# Power_Supplies.net
KiCad netlist of a schematic drawn in Altium Designer
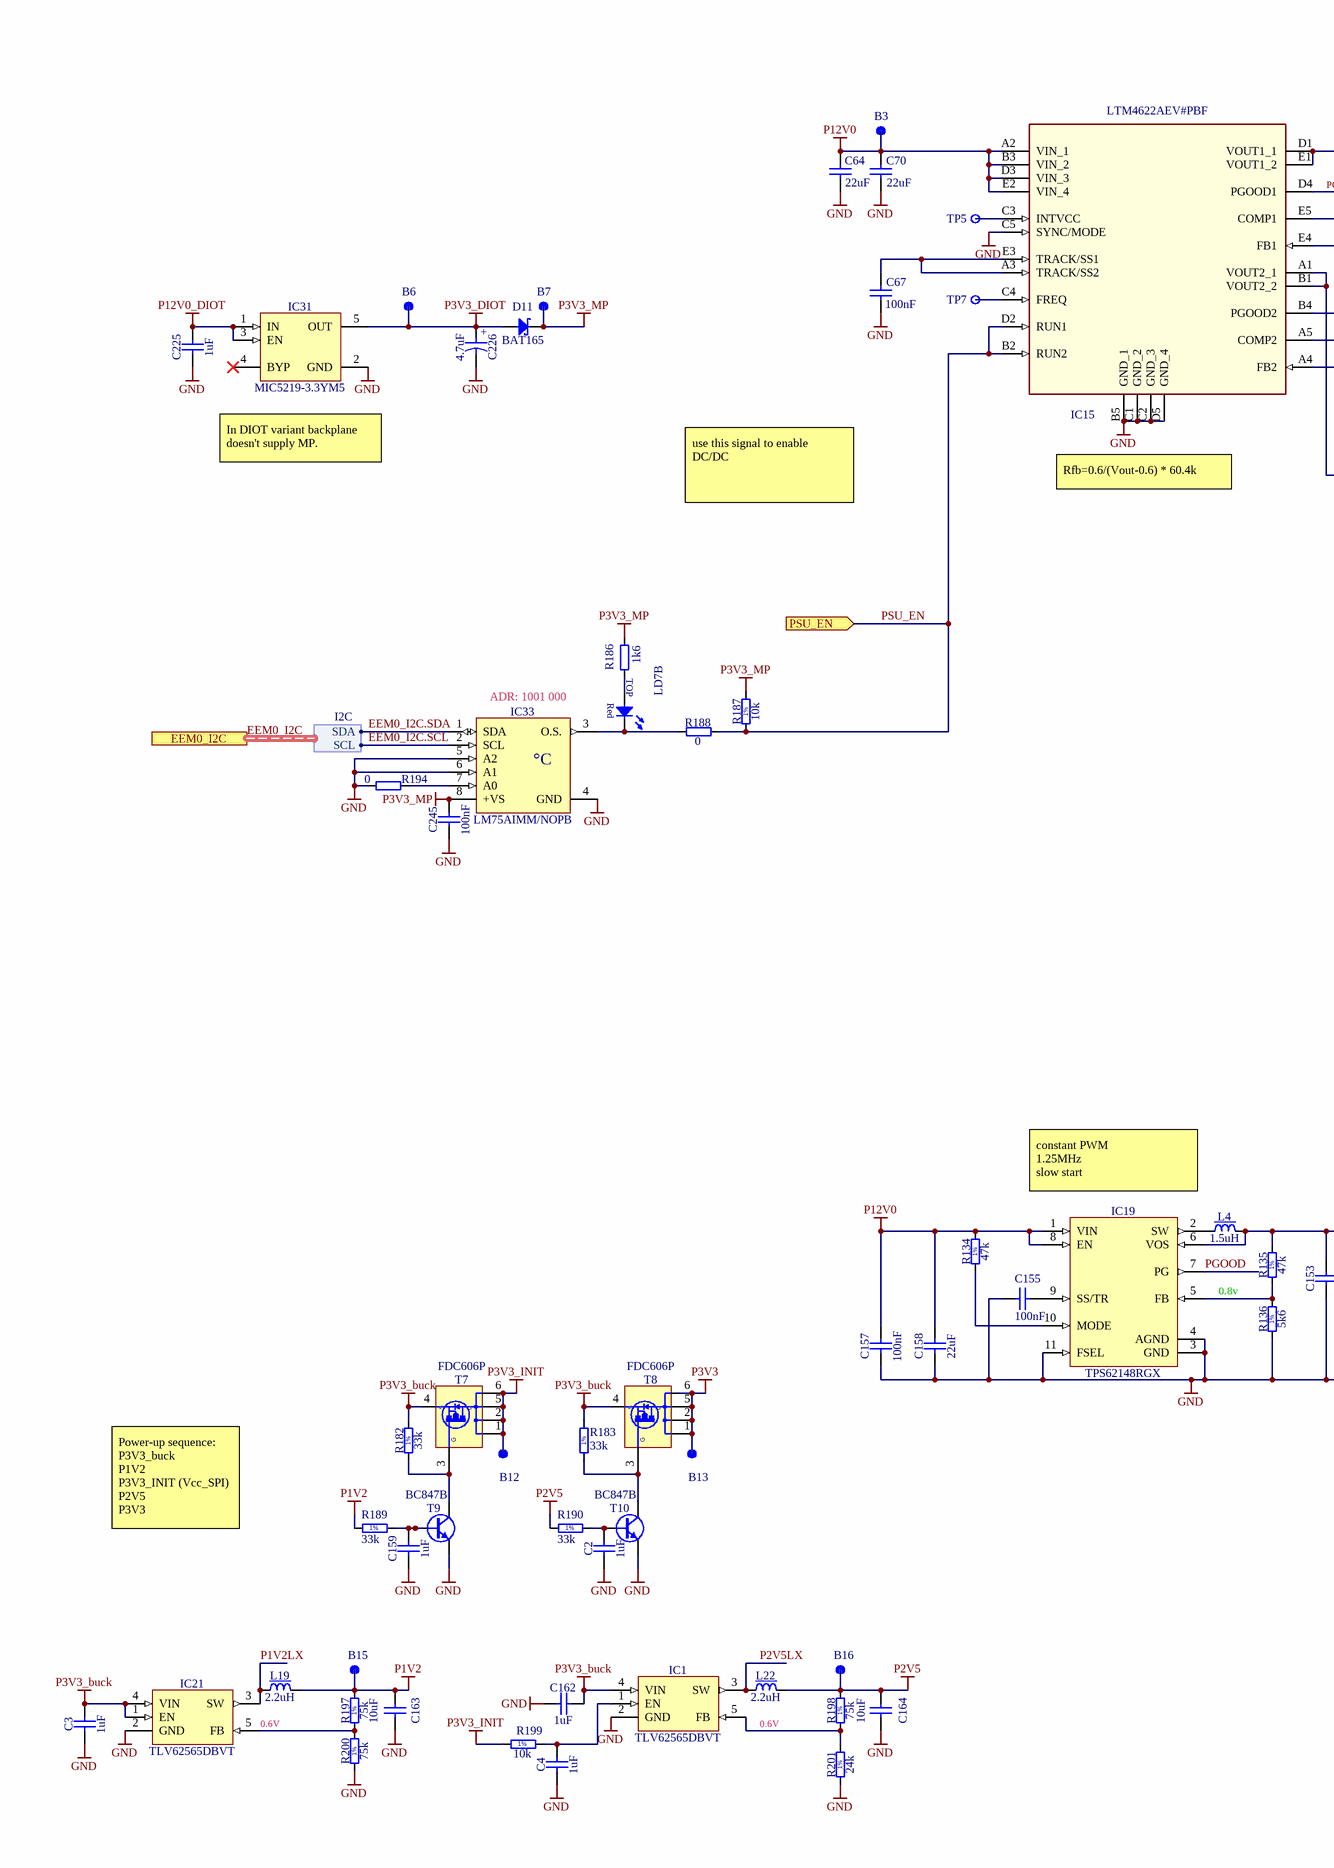
[diagram p0: Power_Supplies.SchDoc, left]
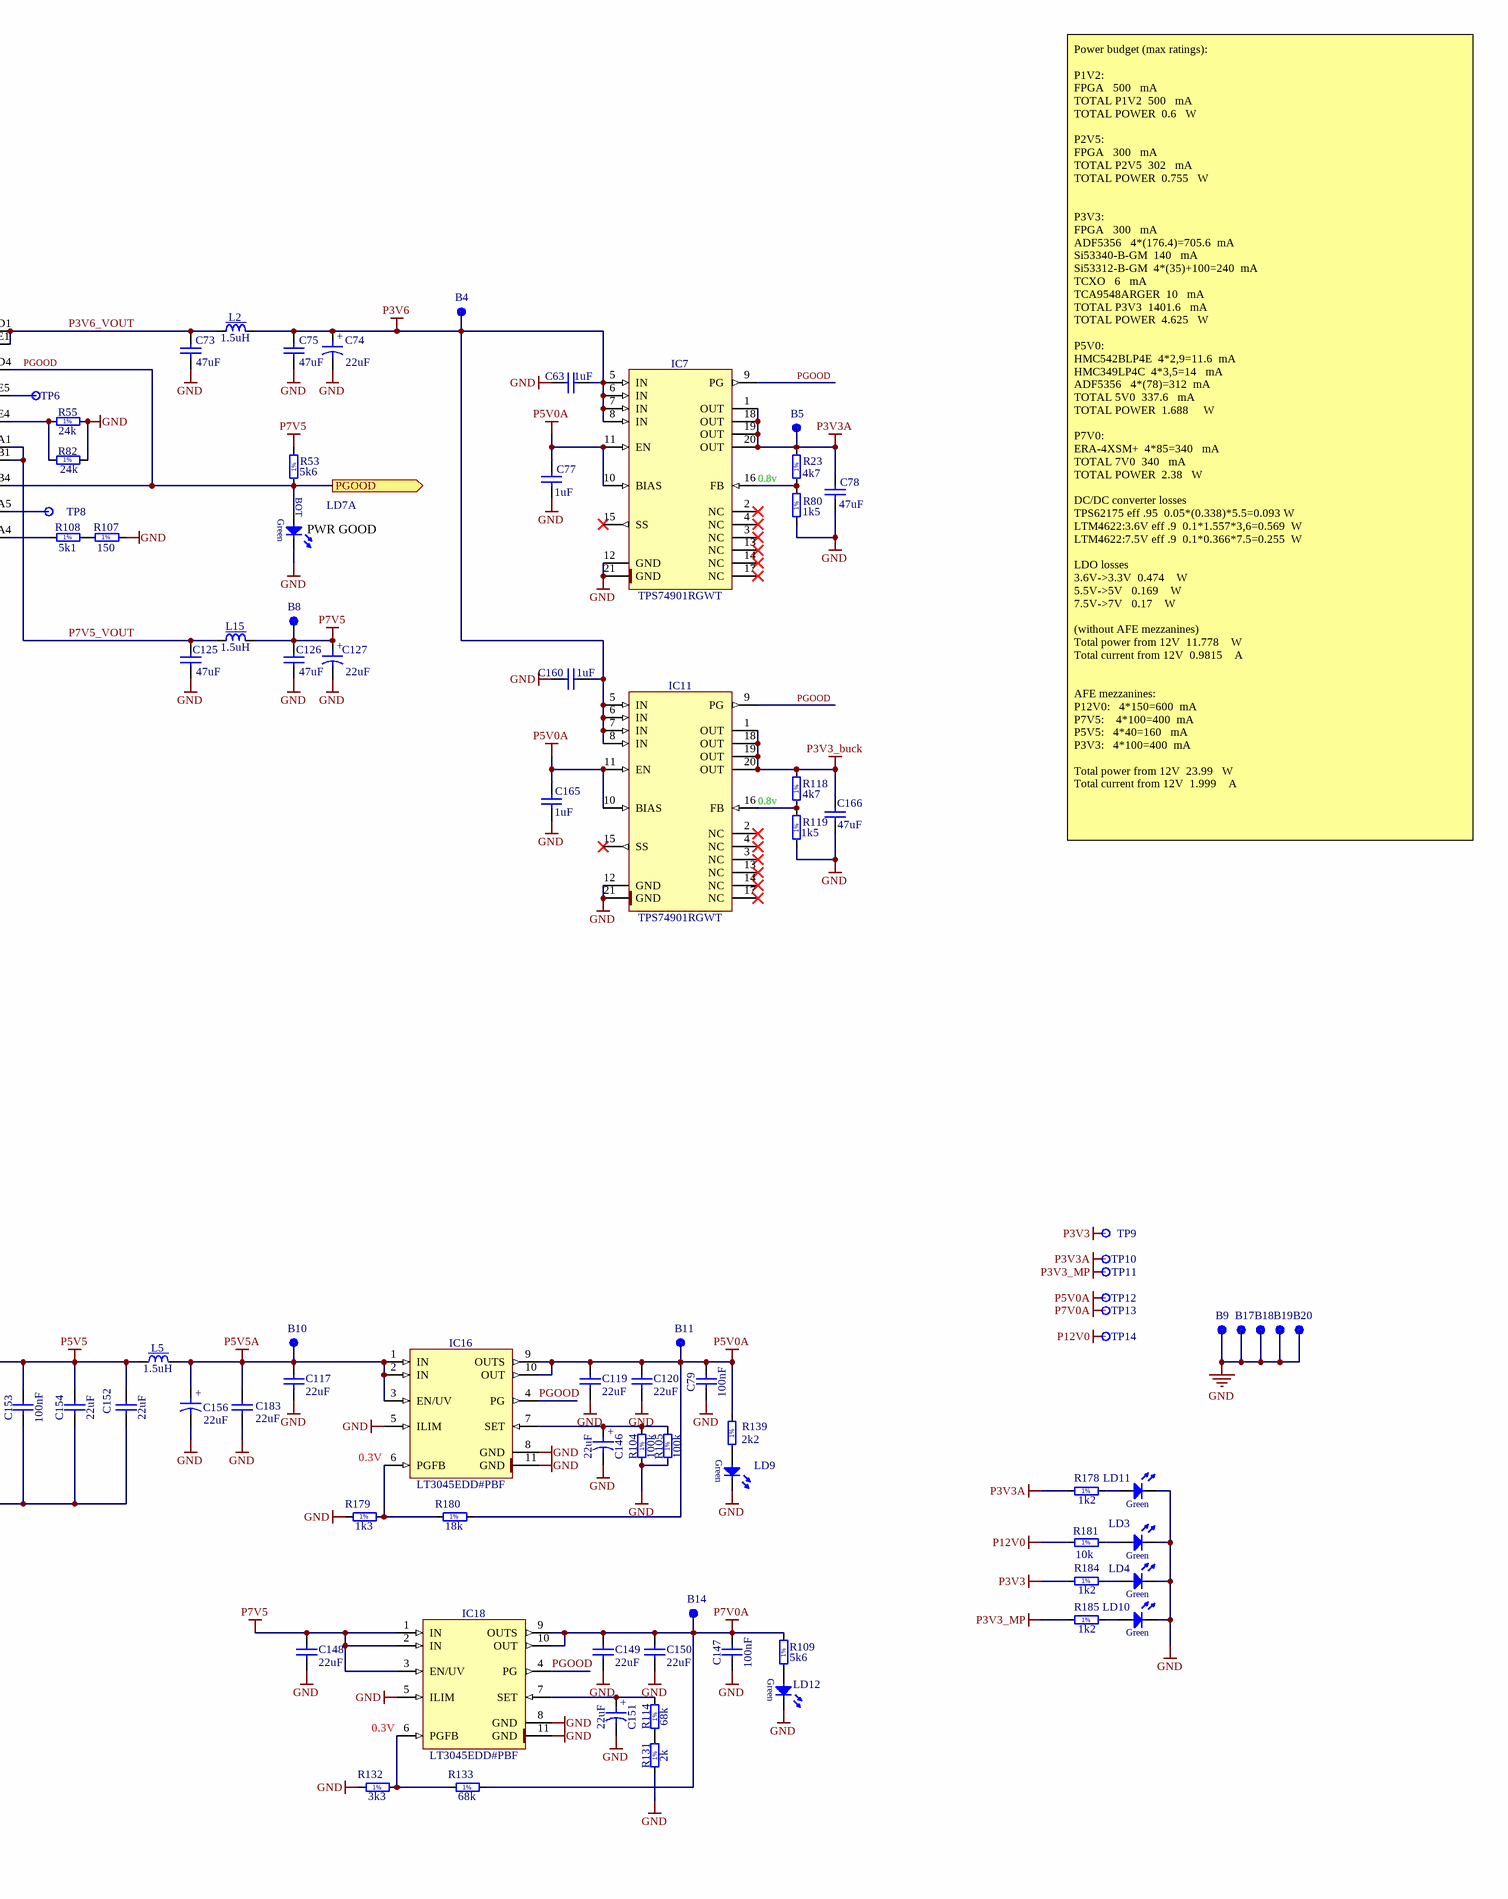
[diagram p1: Power_Supplies.SchDoc, right]

(export (version "E")
  (design (tool "Eeschema 10.0.6"))
  (components
    (comp (ref "B3")
      (value "SMD Pad")
      (footprint "C75")
      (description "Pad")
      (fields (field (name "PART NUMBER") "SMD_PAD_D0.75MM") (field (name "AUTHOR") "CERN DEM BC"))
      (libsource (lib "Eletro-mechanical") (part "Single SMD Pad (Round)"))
    )
    (comp (ref "B4")
      (value "SMD Pad")
      (footprint "C75")
      (description "Pad")
      (fields (field (name "PART NUMBER") "SMD_PAD_D0.75MM") (field (name "AUTHOR") "CERN DEM BC"))
      (libsource (lib "Eletro-mechanical") (part "Single SMD Pad (Round)"))
    )
    (comp (ref "B5")
      (value "SMD Pad")
      (footprint "C75")
      (description "Pad")
      (fields (field (name "PART NUMBER") "SMD_PAD_D0.75MM") (field (name "AUTHOR") "CERN DEM BC"))
      (libsource (lib "Eletro-mechanical") (part "Single SMD Pad (Round)"))
    )
    (comp (ref "B6")
      (value "SMD Pad")
      (footprint "C75")
      (description "Pad")
      (fields (field (name "PART NUMBER") "SMD_PAD_D0.75MM") (field (name "AUTHOR") "CERN DEM BC"))
      (libsource (lib "Eletro-mechanical") (part "Single SMD Pad (Round)"))
    )
    (comp (ref "B7")
      (value "SMD Pad")
      (footprint "C75")
      (description "Pad")
      (fields (field (name "PART NUMBER") "SMD_PAD_D0.75MM") (field (name "AUTHOR") "CERN DEM BC"))
      (libsource (lib "Eletro-mechanical") (part "Single SMD Pad (Round)"))
    )
    (comp (ref "B8")
      (value "SMD Pad")
      (footprint "C75")
      (description "Pad")
      (fields (field (name "PART NUMBER") "SMD_PAD_D0.75MM") (field (name "AUTHOR") "CERN DEM BC"))
      (libsource (lib "Eletro-mechanical") (part "Single SMD Pad (Round)"))
    )
    (comp (ref "B9")
      (value "SMD Pad")
      (footprint "C75")
      (description "Pad")
      (fields (field (name "PART NUMBER") "SMD_PAD_D0.75MM") (field (name "AUTHOR") "CERN DEM BC"))
      (libsource (lib "Eletro-mechanical") (part "Single SMD Pad (Round)"))
    )
    (comp (ref "B10")
      (value "SMD Pad")
      (footprint "C75")
      (description "Pad")
      (fields (field (name "PART NUMBER") "SMD_PAD_D0.75MM") (field (name "AUTHOR") "CERN DEM BC"))
      (libsource (lib "Eletro-mechanical") (part "Single SMD Pad (Round)"))
    )
    (comp (ref "B11")
      (value "SMD Pad")
      (footprint "C75")
      (description "Pad")
      (fields (field (name "PART NUMBER") "SMD_PAD_D0.75MM") (field (name "AUTHOR") "CERN DEM BC"))
      (libsource (lib "Eletro-mechanical") (part "Single SMD Pad (Round)"))
    )
    (comp (ref "B12")
      (value "SMD Pad")
      (footprint "C75")
      (description "Pad")
      (fields (field (name "PART NUMBER") "SMD_PAD_D0.75MM") (field (name "AUTHOR") "CERN DEM BC"))
      (libsource (lib "Eletro-mechanical") (part "Single SMD Pad (Round)"))
    )
    (comp (ref "B13")
      (value "SMD Pad")
      (footprint "C75")
      (description "Pad")
      (fields (field (name "PART NUMBER") "SMD_PAD_D0.75MM") (field (name "AUTHOR") "CERN DEM BC"))
      (libsource (lib "Eletro-mechanical") (part "Single SMD Pad (Round)"))
    )
    (comp (ref "B14")
      (value "SMD Pad")
      (footprint "C75")
      (description "Pad")
      (fields (field (name "PART NUMBER") "SMD_PAD_D0.75MM") (field (name "AUTHOR") "CERN DEM BC"))
      (libsource (lib "Eletro-mechanical") (part "Single SMD Pad (Round)"))
    )
    (comp (ref "B15")
      (value "SMD Pad")
      (footprint "C75")
      (description "Pad")
      (fields (field (name "PART NUMBER") "SMD_PAD_D0.75MM") (field (name "AUTHOR") "CERN DEM BC"))
      (libsource (lib "Eletro-mechanical") (part "Single SMD Pad (Round)"))
    )
    (comp (ref "B16")
      (value "SMD Pad")
      (footprint "C75")
      (description "Pad")
      (fields (field (name "PART NUMBER") "SMD_PAD_D0.75MM") (field (name "AUTHOR") "CERN DEM BC"))
      (libsource (lib "Eletro-mechanical") (part "Single SMD Pad (Round)"))
    )
    (comp (ref "B17")
      (value "SMD Pad")
      (footprint "C75")
      (description "Pad")
      (fields (field (name "PART NUMBER") "SMD_PAD_D0.75MM") (field (name "AUTHOR") "CERN DEM BC"))
      (libsource (lib "Eletro-mechanical") (part "Single SMD Pad (Round)"))
    )
    (comp (ref "B18")
      (value "SMD Pad")
      (footprint "C75")
      (description "Pad")
      (fields (field (name "PART NUMBER") "SMD_PAD_D0.75MM") (field (name "AUTHOR") "CERN DEM BC"))
      (libsource (lib "Eletro-mechanical") (part "Single SMD Pad (Round)"))
    )
    (comp (ref "B19")
      (value "SMD Pad")
      (footprint "C75")
      (description "Pad")
      (fields (field (name "PART NUMBER") "SMD_PAD_D0.75MM") (field (name "AUTHOR") "CERN DEM BC"))
      (libsource (lib "Eletro-mechanical") (part "Single SMD Pad (Round)"))
    )
    (comp (ref "B20")
      (value "SMD Pad")
      (footprint "C75")
      (description "Pad")
      (fields (field (name "PART NUMBER") "SMD_PAD_D0.75MM") (field (name "AUTHOR") "CERN DEM BC"))
      (libsource (lib "Eletro-mechanical") (part "Single SMD Pad (Round)"))
    )
    (comp (ref "C2")
      (value "1uF")
      (footprint "CAPC1608X87N")
      (description "Non-polarised capacitor")
      (fields
        (field (name "PART NUMBER") "CC0603_1UF_25V_10%_X7R")
        (field (name "VOLTAGE") "25V")
        (field (name "AUTHOR") "CERN DEM JLC")
      )
      (libsource (lib "Capacitors") (part "Capacitor - non polarized"))
    )
    (comp (ref "C3")
      (value "1uF")
      (footprint "CAPC1005X55N")
      (description "Non-polarised capacitor")
      (fields
        (field (name "PART NUMBER") "CC0402_1UF_16V_10%_X5R")
        (field (name "VOLTAGE") "16V")
        (field (name "AUTHOR") "CERN DEM JLC")
      )
      (libsource (lib "Capacitors") (part "Capacitor - non polarized"))
    )
    (comp (ref "C4")
      (value "1uF")
      (footprint "CAPC1608X87N")
      (description "Non-polarised capacitor")
      (fields
        (field (name "PART NUMBER") "CC0603_1UF_25V_10%_X7R")
        (field (name "VOLTAGE") "25V")
        (field (name "AUTHOR") "CERN DEM JLC")
      )
      (libsource (lib "Capacitors") (part "Capacitor - non polarized"))
    )
    (comp (ref "C63")
      (value "1uF")
      (footprint "CAPC1005X55N")
      (description "Non-polarised capacitor")
      (fields
        (field (name "PART NUMBER") "CC0402_1UF_16V_10%_X5R")
        (field (name "VOLTAGE") "16V")
        (field (name "AUTHOR") "CERN DEM JLC")
      )
      (libsource (lib "Capacitors") (part "Capacitor - non polarized"))
    )
    (comp (ref "C64")
      (value "22uF")
      (footprint "CAPC2012X135N")
      (description "Non-polarised capacitor")
      (fields
        (field (name "PART NUMBER") "CC0805_22UF_16V_10%_X5R")
        (field (name "VOLTAGE") "16V")
        (field (name "AUTHOR") "CERN DEM JLC")
      )
      (libsource (lib "Capacitors") (part "Capacitor - non polarized"))
    )
    (comp (ref "C67")
      (value "100nF")
      (footprint "CAPC1005X55N")
      (description "Non-polarised capacitor")
      (fields
        (field (name "PART NUMBER") "CC0402_100NF_16V_10%_X5R")
        (field (name "VOLTAGE") "16V")
        (field (name "AUTHOR") "CERN DEM JLC")
      )
      (libsource (lib "Capacitors") (part "Capacitor - non polarized"))
    )
    (comp (ref "C70")
      (value "22uF")
      (footprint "CAPC2012X135N")
      (description "Non-polarised capacitor")
      (fields
        (field (name "PART NUMBER") "CC0805_22UF_16V_10%_X5R")
        (field (name "VOLTAGE") "16V")
        (field (name "AUTHOR") "CERN DEM JLC")
      )
      (libsource (lib "Capacitors") (part "Capacitor - non polarized"))
    )
    (comp (ref "C73")
      (value "47uF")
      (footprint "CAPC3225X270N")
      (description "Non-polarised capacitor")
      (fields
        (field (name "PART NUMBER") "CC1210_47UF_10V_20%_X5R")
        (field (name "VOLTAGE") "10V")
        (field (name "AUTHOR") "CERN DEM JLC")
      )
      (libsource (lib "Capacitors") (part "Capacitor - non polarized"))
    )
    (comp (ref "C74")
      (value "22uF")
      (footprint "CAPMP3528X210N")
      (description "Polarised capacitor")
      (fields
        (field (name "PART NUMBER") "CTE3528-21_22UF_10V_10%_LESR0700")
        (field (name "VOLTAGE") "10V")
        (field (name "AUTHOR") "CERN DEM JLC")
      )
      (libsource (lib "Capacitors") (part "Capacitor - polarized"))
    )
    (comp (ref "C75")
      (value "47uF")
      (footprint "CAPC3225X270N")
      (description "Non-polarised capacitor")
      (fields
        (field (name "PART NUMBER") "CC1210_47UF_10V_20%_X5R")
        (field (name "VOLTAGE") "10V")
        (field (name "AUTHOR") "CERN DEM JLC")
      )
      (libsource (lib "Capacitors") (part "Capacitor - non polarized"))
    )
    (comp (ref "C77")
      (value "1uF")
      (footprint "CAPC1005X55N")
      (description "Non-polarised capacitor")
      (fields
        (field (name "PART NUMBER") "CC0402_1UF_16V_10%_X5R")
        (field (name "VOLTAGE") "16V")
        (field (name "AUTHOR") "CERN DEM JLC")
      )
      (libsource (lib "Capacitors") (part "Capacitor - non polarized"))
    )
    (comp (ref "C78")
      (value "47uF")
      (footprint "CAPC3225X270N")
      (description "Non-polarised capacitor")
      (fields
        (field (name "PART NUMBER") "CC1210_47UF_10V_20%_X5R")
        (field (name "VOLTAGE") "10V")
        (field (name "AUTHOR") "CERN DEM JLC")
      )
      (libsource (lib "Capacitors") (part "Capacitor - non polarized"))
    )
    (comp (ref "C79")
      (value "100nF")
      (footprint "CAPC1005X55N")
      (description "Non-polarised capacitor")
      (fields
        (field (name "PART NUMBER") "CC0402_100NF_16V_10%_X5R")
        (field (name "VOLTAGE") "16V")
        (field (name "AUTHOR") "CERN DEM JLC")
      )
      (libsource (lib "Capacitors") (part "Capacitor - non polarized"))
    )
    (comp (ref "C117")
      (value "22uF")
      (footprint "CAPC2012X135N")
      (description "Non-polarised capacitor")
      (fields
        (field (name "PART NUMBER") "CC0805_22UF_16V_10%_X5R")
        (field (name "VOLTAGE") "16V")
        (field (name "AUTHOR") "CERN DEM JLC")
      )
      (libsource (lib "Capacitors") (part "Capacitor - non polarized"))
    )
    (comp (ref "C119")
      (value "22uF")
      (footprint "CAPC2012X135N")
      (description "Non-polarised capacitor")
      (fields
        (field (name "PART NUMBER") "CC0805_22UF_16V_10%_X5R")
        (field (name "VOLTAGE") "16V")
        (field (name "AUTHOR") "CERN DEM JLC")
      )
      (libsource (lib "Capacitors") (part "Capacitor - non polarized"))
    )
    (comp (ref "C120")
      (value "22uF")
      (footprint "CAPC2012X135N")
      (description "Non-polarised capacitor")
      (fields
        (field (name "PART NUMBER") "CC0805_22UF_16V_10%_X5R")
        (field (name "VOLTAGE") "16V")
        (field (name "AUTHOR") "CERN DEM JLC")
      )
      (libsource (lib "Capacitors") (part "Capacitor - non polarized"))
    )
    (comp (ref "C125")
      (value "47uF")
      (footprint "CAPC3225X270N")
      (description "Non-polarised capacitor")
      (fields
        (field (name "PART NUMBER") "CC1210_47UF_10V_20%_X5R")
        (field (name "VOLTAGE") "10V")
        (field (name "AUTHOR") "CERN DEM JLC")
      )
      (libsource (lib "Capacitors") (part "Capacitor - non polarized"))
    )
    (comp (ref "C126")
      (value "47uF")
      (footprint "CAPC3225X270N")
      (description "Non-polarised capacitor")
      (fields
        (field (name "PART NUMBER") "CC1210_47UF_10V_20%_X5R")
        (field (name "VOLTAGE") "10V")
        (field (name "AUTHOR") "CERN DEM JLC")
      )
      (libsource (lib "Capacitors") (part "Capacitor - non polarized"))
    )
    (comp (ref "C127")
      (value "22uF")
      (footprint "CAPMP3528X210N")
      (description "Polarised capacitor")
      (fields
        (field (name "PART NUMBER") "CTE3528-21_22UF_10V_10%_LESR0700")
        (field (name "VOLTAGE") "10V")
        (field (name "AUTHOR") "CERN DEM JLC")
      )
      (libsource (lib "Capacitors") (part "Capacitor - polarized"))
    )
    (comp (ref "C146")
      (value "22uF")
      (footprint "CAPMP3528X210N")
      (description "Polarised capacitor")
      (fields
        (field (name "PART NUMBER") "CTE3528-21_22UF_10V_10%_LESR0700")
        (field (name "VOLTAGE") "10V")
        (field (name "AUTHOR") "CERN DEM JLC")
      )
      (libsource (lib "Capacitors") (part "Capacitor - polarized"))
    )
    (comp (ref "C147")
      (value "100nF")
      (footprint "CAPC1005X55N")
      (description "Non-polarised capacitor")
      (fields
        (field (name "PART NUMBER") "CC0402_100NF_16V_10%_X5R")
        (field (name "VOLTAGE") "16V")
        (field (name "AUTHOR") "CERN DEM JLC")
      )
      (libsource (lib "Capacitors") (part "Capacitor - non polarized"))
    )
    (comp (ref "C148")
      (value "22uF")
      (footprint "CAPC2012X135N")
      (description "Non-polarised capacitor")
      (fields
        (field (name "PART NUMBER") "CC0805_22UF_16V_10%_X5R")
        (field (name "VOLTAGE") "16V")
        (field (name "AUTHOR") "CERN DEM JLC")
      )
      (libsource (lib "Capacitors") (part "Capacitor - non polarized"))
    )
    (comp (ref "C149")
      (value "22uF")
      (footprint "CAPC2012X135N")
      (description "Non-polarised capacitor")
      (fields
        (field (name "PART NUMBER") "CC0805_22UF_16V_10%_X5R")
        (field (name "VOLTAGE") "16V")
        (field (name "AUTHOR") "CERN DEM JLC")
      )
      (libsource (lib "Capacitors") (part "Capacitor - non polarized"))
    )
    (comp (ref "C150")
      (value "22uF")
      (footprint "CAPC2012X135N")
      (description "Non-polarised capacitor")
      (fields
        (field (name "PART NUMBER") "CC0805_22UF_16V_10%_X5R")
        (field (name "VOLTAGE") "16V")
        (field (name "AUTHOR") "CERN DEM JLC")
      )
      (libsource (lib "Capacitors") (part "Capacitor - non polarized"))
    )
    (comp (ref "C151")
      (value "22uF")
      (footprint "CAPMP3528X210N")
      (description "Polarised capacitor")
      (fields
        (field (name "PART NUMBER") "CTE3528-21_22UF_10V_10%_LESR0700")
        (field (name "VOLTAGE") "10V")
        (field (name "AUTHOR") "CERN DEM JLC")
      )
      (libsource (lib "Capacitors") (part "Capacitor - polarized"))
    )
    (comp (ref "C152")
      (value "22uF")
      (footprint "CAPC2012X135N")
      (description "Non-polarised capacitor")
      (fields
        (field (name "PART NUMBER") "CC0805_22UF_16V_10%_X5R")
        (field (name "VOLTAGE") "16V")
        (field (name "AUTHOR") "CERN DEM JLC")
      )
      (libsource (lib "Capacitors") (part "Capacitor - non polarized"))
    )
    (comp (ref "C153")
      (value "100nF")
      (footprint "CAPC1005X55N")
      (description "Non-polarised capacitor")
      (fields
        (field (name "PART NUMBER") "CC0402_100NF_16V_10%_X5R")
        (field (name "VOLTAGE") "16V")
        (field (name "AUTHOR") "CERN DEM JLC")
      )
      (libsource (lib "Capacitors") (part "Capacitor - non polarized"))
    )
    (comp (ref "C154")
      (value "22uF")
      (footprint "CAPC2012X135N")
      (description "Non-polarised capacitor")
      (fields
        (field (name "PART NUMBER") "CC0805_22UF_16V_10%_X5R")
        (field (name "VOLTAGE") "16V")
        (field (name "AUTHOR") "CERN DEM JLC")
      )
      (libsource (lib "Capacitors") (part "Capacitor - non polarized"))
    )
    (comp (ref "C155")
      (value "100nF")
      (footprint "CAPC1005X55N")
      (description "Non-polarised capacitor")
      (fields
        (field (name "PART NUMBER") "CC0402_100NF_16V_10%_X5R")
        (field (name "VOLTAGE") "16V")
        (field (name "AUTHOR") "CERN DEM JLC")
      )
      (libsource (lib "Capacitors") (part "Capacitor - non polarized"))
    )
    (comp (ref "C156")
      (value "22uF")
      (footprint "CAPMP3528X210N")
      (description "Polarised capacitor")
      (fields
        (field (name "PART NUMBER") "CTE3528-21_22UF_10V_10%_LESR0700")
        (field (name "VOLTAGE") "10V")
        (field (name "AUTHOR") "CERN DEM JLC")
      )
      (libsource (lib "Capacitors") (part "Capacitor - polarized"))
    )
    (comp (ref "C157")
      (value "100nF")
      (footprint "CAPC1005X55N")
      (description "Non-polarised capacitor")
      (fields
        (field (name "PART NUMBER") "CC0402_100NF_16V_10%_X5R")
        (field (name "VOLTAGE") "16V")
        (field (name "AUTHOR") "CERN DEM JLC")
      )
      (libsource (lib "Capacitors") (part "Capacitor - non polarized"))
    )
    (comp (ref "C158")
      (value "22uF")
      (footprint "CAPC2012X135N")
      (description "Non-polarised capacitor")
      (fields
        (field (name "PART NUMBER") "CC0805_22UF_16V_10%_X5R")
        (field (name "VOLTAGE") "16V")
        (field (name "AUTHOR") "CERN DEM JLC")
      )
      (libsource (lib "Capacitors") (part "Capacitor - non polarized"))
    )
    (comp (ref "C159")
      (value "1uF")
      (footprint "CAPC1608X87N")
      (description "Non-polarised capacitor")
      (fields
        (field (name "PART NUMBER") "CC0603_1UF_25V_10%_X7R")
        (field (name "VOLTAGE") "25V")
        (field (name "AUTHOR") "CERN DEM JLC")
      )
      (libsource (lib "Capacitors") (part "Capacitor - non polarized"))
    )
    (comp (ref "C160")
      (value "1uF")
      (footprint "CAPC1005X55N")
      (description "Non-polarised capacitor")
      (fields
        (field (name "PART NUMBER") "CC0402_1UF_16V_10%_X5R")
        (field (name "VOLTAGE") "16V")
        (field (name "AUTHOR") "CERN DEM JLC")
      )
      (libsource (lib "Capacitors") (part "Capacitor - non polarized"))
    )
    (comp (ref "C162")
      (value "1uF")
      (footprint "CAPC1005X55N")
      (description "Non-polarised capacitor")
      (fields
        (field (name "PART NUMBER") "CC0402_1UF_16V_10%_X5R")
        (field (name "VOLTAGE") "16V")
        (field (name "AUTHOR") "CERN DEM JLC")
      )
      (libsource (lib "Capacitors") (part "Capacitor - non polarized"))
    )
    (comp (ref "C163")
      (value "10uF")
      (footprint "CAPC2012X135N")
      (description "Non-polarised capacitor")
      (fields
        (field (name "PART NUMBER") "CC0805_10UF_16V_10%_X5R")
        (field (name "VOLTAGE") "16V")
        (field (name "AUTHOR") "CERN DEM JLC")
      )
      (libsource (lib "Capacitors") (part "Capacitor - non polarized"))
    )
    (comp (ref "C164")
      (value "10uF")
      (footprint "CAPC2012X135N")
      (description "Non-polarised capacitor")
      (fields
        (field (name "PART NUMBER") "CC0805_10UF_16V_10%_X5R")
        (field (name "VOLTAGE") "16V")
        (field (name "AUTHOR") "CERN DEM JLC")
      )
      (libsource (lib "Capacitors") (part "Capacitor - non polarized"))
    )
    (comp (ref "C165")
      (value "1uF")
      (footprint "CAPC1005X55N")
      (description "Non-polarised capacitor")
      (fields
        (field (name "PART NUMBER") "CC0402_1UF_16V_10%_X5R")
        (field (name "VOLTAGE") "16V")
        (field (name "AUTHOR") "CERN DEM JLC")
      )
      (libsource (lib "Capacitors") (part "Capacitor - non polarized"))
    )
    (comp (ref "C166")
      (value "47uF")
      (footprint "CAPC3225X270N")
      (description "Non-polarised capacitor")
      (fields
        (field (name "PART NUMBER") "CC1210_47UF_10V_20%_X5R")
        (field (name "VOLTAGE") "10V")
        (field (name "AUTHOR") "CERN DEM JLC")
      )
      (libsource (lib "Capacitors") (part "Capacitor - non polarized"))
    )
    (comp (ref "C183")
      (value "22uF")
      (footprint "CAPC2012X135N")
      (description "Non-polarised capacitor")
      (fields
        (field (name "PART NUMBER") "CC0805_22UF_16V_10%_X5R")
        (field (name "VOLTAGE") "16V")
        (field (name "AUTHOR") "CERN DEM JLC")
      )
      (libsource (lib "Capacitors") (part "Capacitor - non polarized"))
    )
    (comp (ref "C225")
      (value "1uF")
      (footprint "CAPC1608X87N")
      (description "Non-polarised capacitor")
      (fields
        (field (name "PART NUMBER") "CC0603_1UF_25V_10%_X7R")
        (field (name "VOLTAGE") "25V")
        (field (name "AUTHOR") "CERN DEM JLC")
      )
      (libsource (lib "Capacitors") (part "Capacitor - non polarized"))
    )
    (comp (ref "C226")
      (value "4.7uF")
      (footprint "CAPMP3216X180N")
      (description "Polarised capacitor")
      (fields
        (field (name "PART NUMBER") "CTE3216-18_4.7UF_10V_10%_AVX_TPSA475K010T1400")
        (field (name "VOLTAGE") "10V")
        (field (name "AUTHOR") "CERN DEM JLC")
      )
      (libsource (lib "Capacitors") (part "Capacitor - polarized"))
    )
    (comp (ref "C245")
      (value "100nF")
      (footprint "CAPC1005X55N")
      (description "Non-polarised capacitor")
      (fields
        (field (name "PART NUMBER") "CC0402_100NF_16V_10%_X5R")
        (field (name "VOLTAGE") "16V")
        (field (name "AUTHOR") "CERN DEM JLC")
      )
      (libsource (lib "Capacitors") (part "Capacitor - non polarized"))
    )
    (comp (ref "D11")
      (value "BAT165")
      (footprint "SOD2512X110N")
      (description "Schottky Diode")
      (fields
        (field (name "MANUFACTURER") "INFINEON")
        (field (name "VOLTAGE") "40V")
        (field (name "AUTHOR") "CERN DEM JLC")
      )
      (libsource (lib "ICs And Semiconductors") (part "Diode Schottky"))
    )
    (comp (ref "IC1")
      (value "TLV62565DBVT")
      (footprint "SOT95P280X145-5N")
      (description "1.5A High Efficiency Step-Down Converter, Adjustable Output Voltage")
      (fields
        (field (name "MANUFACTURER") "TEXAS INSTRUMENTS")
        (field (name "MANUFACTURER PART NUMBER") "TLV62565DBV")
        (field (name "AUTHOR") "CERN DEM JMW")
      )
      (libsource (lib "ICs And Semiconductors") (part "TLV62565"))
    )
    (comp (ref "IC7")
      (value "TPS74901RGWT")
      (footprint "QFN65P500X500X100-21N-S325")
      (description "3A, 0.8 to 3.6V Adjustable Low-Dropout Linear Regulator with Programmable Soft-Start")
      (fields (field (name "MANUFACTURER") "TEXAS INSTRUMENTS") (field (name "AUTHOR") "CERN DEM JLC"))
      (libsource (lib "ICs And Semiconductors") (part "TPS74901RGWT"))
    )
    (comp (ref "IC11")
      (value "TPS74901RGWT")
      (footprint "QFN65P500X500X100-21N-S325")
      (description "3A, 0.8 to 3.6V Adjustable Low-Dropout Linear Regulator with Programmable Soft-Start")
      (fields (field (name "MANUFACTURER") "TEXAS INSTRUMENTS") (field (name "AUTHOR") "CERN DEM JLC"))
      (libsource (lib "ICs And Semiconductors") (part "TPS74901RGWT"))
    )
    (comp (ref "IC15")
      (value "LTM4622AEV#PBF")
      (footprint "LGA25C127P5X5_625X625X190")
      (description "Dual Ultrathin 2A or Single 4A, 3.6V to 20V, 1.5V to 12V   Step-Down DC/DC μModule Regulator")
      (fields (field (name "MANUFACTURER") "LINEAR TECHNOLOGY") (field (name "AUTHOR") "GK"))
      (libsource (lib "LIBRARY_SCH") (part "PM_LTM4622"))
    )
    (comp (ref "IC16")
      (value "LT3045EDD#PBF")
      (footprint "SON50P300X300X80-11N-R175X248")
      (description "20V, 500mA, Ultralow Noise, Ultrahigh PSRR Linear Regulator")
      (fields (field (name "MANUFACTURER") "LINEAR TECHNOLOGY") (field (name "AUTHOR") "CERN DEM JLC"))
      (libsource (lib "ICs And Semiconductors") (part "LT3045EDD"))
    )
    (comp (ref "IC18")
      (value "LT3045EDD#PBF")
      (footprint "SON50P300X300X80-11N-R175X248")
      (description "20V, 500mA, Ultralow Noise, Ultrahigh PSRR Linear Regulator")
      (fields (field (name "MANUFACTURER") "LINEAR TECHNOLOGY") (field (name "AUTHOR") "CERN DEM JLC"))
      (libsource (lib "ICs And Semiconductors") (part "LT3045EDD"))
    )
    (comp (ref "IC19")
      (value "TPS62148RGX")
      (footprint "TEXAS_RGX0011A")
      (description "3V-17V 2A Step-Down Converter, High Accuracy, With DCS-Control")
      (fields (field (name "MANUFACTURER") "TEXAS INSTRUMENTS") (field (name "AUTHOR") "CERN DEM MR"))
      (libsource (lib "ICs And Semiconductors") (part "TPS62148"))
    )
    (comp (ref "IC21")
      (value "TLV62565DBVT")
      (footprint "SOT95P280X145-5N")
      (description "1.5A High Efficiency Step-Down Converter, Adjustable Output Voltage")
      (fields
        (field (name "MANUFACTURER") "TEXAS INSTRUMENTS")
        (field (name "MANUFACTURER PART NUMBER") "TLV62565DBV")
        (field (name "AUTHOR") "CERN DEM JMW")
      )
      (libsource (lib "ICs And Semiconductors") (part "TLV62565"))
    )
    (comp (ref "IC31")
      (value "MIC5219-3.3YM5")
      (footprint "SOT95P280X145-5N")
      (description "500mA Peak Output LDO Regulator")
      (fields (field (name "MANUFACTURER") "MICROCHIP TECHNOLOGY") (field (name "AUTHOR") "CERN DEM WB"))
      (libsource (lib "ICs And Semiconductors") (part "MIC5219-X.XYM5"))
    )
    (comp (ref "IC33")
      (value "LM75AIMM/NOPB")
      (footprint "SOP65P490X109-8N")
      (description "Digital Temperature Sensor and Thermal Watchdog with Two-Wire Interface")
      (fields (field (name "MANUFACTURER") "TEXAS INSTRUMENTS") (field (name "AUTHOR") "CERN DEM JLC"))
      (libsource (lib "ICs And Semiconductors") (part "LM75"))
    )
    (comp (ref "L2")
      (value "1.5uH")
      (footprint "IND_TDK_SPM6530")
      (description "Inductor With Core")
      (fields
        (field (name "PART NUMBER") "IND_1.5UH_20%_TDK_SPM6530")
        (field (name "POWER") "11A")
        (field (name "AUTHOR") "CERN DEM MR")
      )
      (libsource (lib "Inductors & Transformers") (part "Inductor With Magnetic core"))
    )
    (comp (ref "L4")
      (value "1.5uH")
      (footprint "IND_TDK_SPM6530")
      (description "Inductor With Core")
      (fields
        (field (name "PART NUMBER") "IND_1.5UH_20%_TDK_SPM6530")
        (field (name "POWER") "11A")
        (field (name "AUTHOR") "CERN DEM MR")
      )
      (libsource (lib "Inductors & Transformers") (part "Inductor With Magnetic core"))
    )
    (comp (ref "L5")
      (value "1.5uH")
      (footprint "IND_TDK_SPM6530")
      (description "Inductor With Core")
      (fields
        (field (name "PART NUMBER") "IND_1.5UH_20%_TDK_SPM6530")
        (field (name "POWER") "11A")
        (field (name "AUTHOR") "CERN DEM MR")
      )
      (libsource (lib "Inductors & Transformers") (part "Inductor With Magnetic core"))
    )
    (comp (ref "L15")
      (value "1.5uH")
      (footprint "IND_TDK_SPM6530")
      (description "Inductor With Core")
      (fields
        (field (name "PART NUMBER") "IND_1.5UH_20%_TDK_SPM6530")
        (field (name "POWER") "11A")
        (field (name "AUTHOR") "CERN DEM MR")
      )
      (libsource (lib "Inductors & Transformers") (part "Inductor With Magnetic core"))
    )
    (comp (ref "L19")
      (value "2.2uH")
      (footprint "IND_MURATA_LQH44PN_P0")
      (description "Inductor With Core")
      (fields
        (field (name "PART NUMBER") "IND_2.2UH_20%_MURATA_LQH44PN2R2MP0L")
        (field (name "POWER") "1.8A")
        (field (name "AUTHOR") "CERN DEM JLC")
      )
      (libsource (lib "Inductors & Transformers") (part "Inductor With Magnetic core"))
    )
    (comp (ref "L22")
      (value "2.2uH")
      (footprint "IND_MURATA_LQH44PN_P0")
      (description "Inductor With Core")
      (fields
        (field (name "PART NUMBER") "IND_2.2UH_20%_MURATA_LQH44PN2R2MP0L")
        (field (name "POWER") "1.8A")
        (field (name "AUTHOR") "CERN DEM JLC")
      )
      (libsource (lib "Inductors & Transformers") (part "Inductor With Magnetic core"))
    )
    (comp (ref "LD3")
      (value "Green")
      (footprint "LED_KINGBRIGHT_KPH-1608CGCKr")
      (description "Green 0603")
      (fields
        (field (name "PART NUMBER") "LED_KINGBRIGHT_KPH-1608CGCK")
        (field (name "MANUFACTURER") "KINGBRIGHT")
        (field (name "AUTHOR") "CERN DEM JLC")
      )
      (libsource (lib "LIBRARY_SCH") (part "LED_0603_Green"))
    )
    (comp (ref "LD4")
      (value "Green")
      (footprint "LED_KINGBRIGHT_KPH-1608CGCKr")
      (description "Green 0603")
      (fields
        (field (name "PART NUMBER") "LED_KINGBRIGHT_KPH-1608CGCK")
        (field (name "MANUFACTURER") "KINGBRIGHT")
        (field (name "AUTHOR") "CERN DEM JLC")
      )
      (libsource (lib "LIBRARY_SCH") (part "LED_0603_Green"))
    )
    (comp (ref "LD7")
      (value "Red/Green")
      (footprint "LED_DIALIGHT_571-0112F")
      (description "2x LED  Botom Green, Top Red")
      (fields
        (field (name "PART NUMBER") "LED_DIALIGHT_571-0112F")
        (field (name "MANUFACTURER") "DIALIGHT")
        (field (name "AUTHOR") "CERN DEM JLC")
      )
      (libsource (lib "ICs And Semiconductors") (part "LED x2 G-1C2A-BOT_R-3C4A-TOP"))
    )
    (comp (ref "LD9")
      (value "Green")
      (footprint "LED_KINGBRIGHT_KPH-1608CGCKr")
      (description "Green 0603")
      (fields
        (field (name "PART NUMBER") "LED_KINGBRIGHT_KPH-1608CGCK")
        (field (name "MANUFACTURER") "KINGBRIGHT")
        (field (name "AUTHOR") "CERN DEM JLC")
      )
      (libsource (lib "LIBRARY_SCH") (part "LED_0603_Green"))
    )
    (comp (ref "LD10")
      (value "Green")
      (footprint "LED_KINGBRIGHT_KPH-1608CGCKr")
      (description "Green 0603")
      (fields
        (field (name "PART NUMBER") "LED_KINGBRIGHT_KPH-1608CGCK")
        (field (name "MANUFACTURER") "KINGBRIGHT")
        (field (name "AUTHOR") "CERN DEM JLC")
      )
      (libsource (lib "LIBRARY_SCH") (part "LED_0603_Green"))
    )
    (comp (ref "LD11")
      (value "Green")
      (footprint "LED_KINGBRIGHT_KPH-1608CGCKr")
      (description "Green 0603")
      (fields
        (field (name "PART NUMBER") "LED_KINGBRIGHT_KPH-1608CGCK")
        (field (name "MANUFACTURER") "KINGBRIGHT")
        (field (name "AUTHOR") "CERN DEM JLC")
      )
      (libsource (lib "LIBRARY_SCH") (part "LED_0603_Green"))
    )
    (comp (ref "LD12")
      (value "Green")
      (footprint "LED_KINGBRIGHT_KPH-1608CGCKr")
      (description "Green 0603")
      (fields
        (field (name "PART NUMBER") "LED_KINGBRIGHT_KPH-1608CGCK")
        (field (name "MANUFACTURER") "KINGBRIGHT")
        (field (name "AUTHOR") "CERN DEM JLC")
      )
      (libsource (lib "LIBRARY_SCH") (part "LED_0603_Green"))
    )
    (comp (ref "R23")
      (value "4k7")
      (footprint "RESC1608X55N")
      (description "Resistor - 1%")
      (fields
        (field (name "PART NUMBER") "R0603_4K7_1%_0.1W_100PPM")
        (field (name "POWER") "0.1W")
        (field (name "AUTHOR") "CERN DEM JLC")
      )
      (libsource (lib "Resistors") (part "Resistor - 1%"))
    )
    (comp (ref "R53")
      (value "5k6")
      (footprint "RESC1608X55N")
      (description "Resistor - 1%")
      (fields
        (field (name "PART NUMBER") "R0603_5K6_1%_0.1W_100PPM")
        (field (name "POWER") "0.1W")
        (field (name "AUTHOR") "CERN DEM JLC")
      )
      (libsource (lib "Resistors") (part "Resistor - 1%"))
    )
    (comp (ref "R55")
      (value "24k")
      (footprint "RESC1608X55N")
      (description "Resistor - 1%")
      (fields
        (field (name "PART NUMBER") "R0603_24K_1%_0.1W_100PPM")
        (field (name "POWER") "0.1W")
        (field (name "AUTHOR") "CERN DEM JLC")
      )
      (libsource (lib "Resistors") (part "Resistor - 1%"))
    )
    (comp (ref "R80")
      (value "1k5")
      (footprint "RESC1608X55N")
      (description "Resistor - 1%")
      (fields
        (field (name "PART NUMBER") "R0603_1K5_1%_0.1W_100PPM")
        (field (name "POWER") "0.1W")
        (field (name "AUTHOR") "CERN DEM JLC")
      )
      (libsource (lib "Resistors") (part "Resistor - 1%"))
    )
    (comp (ref "R82")
      (value "24k")
      (footprint "RESC1608X55N")
      (description "Resistor - 1%")
      (fields
        (field (name "PART NUMBER") "R0603_24K_1%_0.1W_100PPM")
        (field (name "POWER") "0.1W")
        (field (name "AUTHOR") "CERN DEM JLC")
      )
      (libsource (lib "Resistors") (part "Resistor - 1%"))
    )
    (comp (ref "R104")
      (value "100k")
      (footprint "RESC1005X40N")
      (description "Resistor - 1%")
      (fields
        (field (name "PART NUMBER") "R0402_100K_1%_0.0625W_100PPM")
        (field (name "POWER") "0.0625W")
        (field (name "AUTHOR") "CERN DEM JLC")
      )
      (libsource (lib "") (part "Resistor - 1%_1"))
    )
    (comp (ref "R105")
      (value "100k")
      (footprint "RESC1005X40N")
      (description "Resistor - 1%")
      (fields
        (field (name "PART NUMBER") "R0402_100K_1%_0.0625W_100PPM")
        (field (name "POWER") "0.0625W")
        (field (name "AUTHOR") "CERN DEM JLC")
      )
      (libsource (lib "") (part "Resistor - 1%_1"))
    )
    (comp (ref "R107")
      (value "150")
      (footprint "RESC1005X40N")
      (description "Resistor - 1%")
      (fields
        (field (name "PART NUMBER") "R0402_150R_1%_0.0625W_100PPM")
        (field (name "POWER") "0.0625W")
        (field (name "AUTHOR") "CERN DEM JLC")
      )
      (libsource (lib "") (part "Resistor - 1%_1"))
    )
    (comp (ref "R108")
      (value "5k1")
      (footprint "RESC1608X55N")
      (description "Resistor - 1%")
      (fields
        (field (name "PART NUMBER") "R0603_5K1_1%_0.1W_100PPM")
        (field (name "POWER") "0.1W")
        (field (name "AUTHOR") "CERN DEM JLC")
      )
      (libsource (lib "Resistors") (part "Resistor - 1%"))
    )
    (comp (ref "R109")
      (value "5k6")
      (footprint "RESC1608X55N")
      (description "Resistor - 1%")
      (fields
        (field (name "PART NUMBER") "R0603_5K6_1%_0.1W_100PPM")
        (field (name "POWER") "0.1W")
        (field (name "AUTHOR") "CERN DEM JLC")
      )
      (libsource (lib "Resistors") (part "Resistor - 1%"))
    )
    (comp (ref "R114")
      (value "68k")
      (footprint "RESC1005X40N")
      (description "Resistor - 1%")
      (fields
        (field (name "PART NUMBER") "R0402_68K_1%_0.0625W_100PPM")
        (field (name "POWER") "0.0625W")
        (field (name "AUTHOR") "CERN DEM JLC")
      )
      (libsource (lib "") (part "Resistor - 1%_1"))
    )
    (comp (ref "R118")
      (value "4k7")
      (footprint "RESC1608X55N")
      (description "Resistor - 1%")
      (fields
        (field (name "PART NUMBER") "R0603_4K7_1%_0.1W_100PPM")
        (field (name "POWER") "0.1W")
        (field (name "AUTHOR") "CERN DEM JLC")
      )
      (libsource (lib "Resistors") (part "Resistor - 1%"))
    )
    (comp (ref "R119")
      (value "1k5")
      (footprint "RESC1608X55N")
      (description "Resistor - 1%")
      (fields
        (field (name "PART NUMBER") "R0603_1K5_1%_0.1W_100PPM")
        (field (name "POWER") "0.1W")
        (field (name "AUTHOR") "CERN DEM JLC")
      )
      (libsource (lib "Resistors") (part "Resistor - 1%"))
    )
    (comp (ref "R131")
      (value "2k")
      (footprint "RESC1005X40N")
      (description "Resistor - 1%")
      (fields
        (field (name "PART NUMBER") "R0402_2K_1%_0.0625W_100PPM")
        (field (name "POWER") "0.0625W")
        (field (name "AUTHOR") "CERN DEM JLC")
      )
      (libsource (lib "") (part "Resistor - 1%_1"))
    )
    (comp (ref "R132")
      (value "3k3")
      (footprint "RESC1608X55N")
      (description "Resistor - 1%")
      (fields
        (field (name "PART NUMBER") "R0603_3K3_1%_0.1W_100PPM")
        (field (name "POWER") "0.1W")
        (field (name "AUTHOR") "CERN DEM JLC")
      )
      (libsource (lib "Resistors") (part "Resistor - 1%"))
    )
    (comp (ref "R133")
      (value "68k")
      (footprint "RESC1005X40N")
      (description "Resistor - 1%")
      (fields
        (field (name "PART NUMBER") "R0402_68K_1%_0.0625W_100PPM")
        (field (name "POWER") "0.0625W")
        (field (name "AUTHOR") "CERN DEM JLC")
      )
      (libsource (lib "") (part "Resistor - 1%_1"))
    )
    (comp (ref "R134")
      (value "47k")
      (footprint "RESC1005X40N")
      (description "Resistor - 1%")
      (fields
        (field (name "PART NUMBER") "R0402_47K_1%_0.0625W_100PPM")
        (field (name "POWER") "0.0625W")
        (field (name "AUTHOR") "CERN DEM JLC")
      )
      (libsource (lib "") (part "Resistor - 1%_1"))
    )
    (comp (ref "R135")
      (value "47k")
      (footprint "RESC1005X40N")
      (description "Resistor - 1%")
      (fields
        (field (name "PART NUMBER") "R0402_47K_1%_0.0625W_100PPM")
        (field (name "POWER") "0.0625W")
        (field (name "AUTHOR") "CERN DEM JLC")
      )
      (libsource (lib "") (part "Resistor - 1%_1"))
    )
    (comp (ref "R136")
      (value "5k6")
      (footprint "RESC1005X40N")
      (description "Resistor - 1%")
      (fields
        (field (name "PART NUMBER") "R0402_5K6_1%_0.0625W_100PPM")
        (field (name "POWER") "0.0625W")
        (field (name "AUTHOR") "CERN DEM JLC")
      )
      (libsource (lib "") (part "Resistor - 1%_1"))
    )
    (comp (ref "R139")
      (value "2k2")
      (footprint "RESC1608X55N")
      (description "Resistor - 1%")
      (fields
        (field (name "PART NUMBER") "R0603_2K2_1%_0.1W_100PPM")
        (field (name "POWER") "0.1W")
        (field (name "AUTHOR") "CERN DEM JLC")
      )
      (libsource (lib "Resistors") (part "Resistor - 1%"))
    )
    (comp (ref "R178")
      (value "1k2")
      (footprint "RESC1005X40N")
      (description "Resistor - 1%")
      (fields
        (field (name "PART NUMBER") "R0402_1K2_1%_0.0625W_100PPM")
        (field (name "POWER") "0.0625W")
        (field (name "AUTHOR") "CERN DEM JLC")
      )
      (libsource (lib "") (part "Resistor - 1%_1"))
    )
    (comp (ref "R179")
      (value "1k3")
      (footprint "RESC1608X55N")
      (description "Resistor - 1%")
      (fields
        (field (name "PART NUMBER") "R0603_1K3_1%_0.1W_100PPM")
        (field (name "POWER") "0.1W")
        (field (name "AUTHOR") "CERN DEM JLC")
      )
      (libsource (lib "Resistors") (part "Resistor - 1%"))
    )
    (comp (ref "R180")
      (value "18k")
      (footprint "RESC1005X40N")
      (description "Resistor - 1%")
      (fields
        (field (name "PART NUMBER") "R0402_18K_1%_0.0625W_100PPM")
        (field (name "POWER") "0.0625W")
        (field (name "AUTHOR") "CERN DEM JLC")
      )
      (libsource (lib "") (part "Resistor - 1%_1"))
    )
    (comp (ref "R181")
      (value "10k")
      (footprint "RESC1005X40N")
      (description "Resistor - 1%")
      (fields
        (field (name "PART NUMBER") "R0402_10K_1%_0.0625W_100PPM")
        (field (name "POWER") "0.0625W")
        (field (name "AUTHOR") "CERN DEM JLC")
      )
      (libsource (lib "") (part "Resistor - 1%_1"))
    )
    (comp (ref "R182")
      (value "33k")
      (footprint "RESC1005X40N")
      (description "Resistor - 1%")
      (fields
        (field (name "PART NUMBER") "R0402_33K_1%_0.0625W_100PPM")
        (field (name "POWER") "0.0625W")
        (field (name "AUTHOR") "CERN DEM JLC")
      )
      (libsource (lib "") (part "Resistor - 1%_1"))
    )
    (comp (ref "R183")
      (value "33k")
      (footprint "RESC1005X40N")
      (description "Resistor - 1%")
      (fields
        (field (name "PART NUMBER") "R0402_33K_1%_0.0625W_100PPM")
        (field (name "POWER") "0.0625W")
        (field (name "AUTHOR") "CERN DEM JLC")
      )
      (libsource (lib "") (part "Resistor - 1%_1"))
    )
    (comp (ref "R184")
      (value "1k2")
      (footprint "RESC1005X40N")
      (description "Resistor - 1%")
      (fields
        (field (name "PART NUMBER") "R0402_1K2_1%_0.0625W_100PPM")
        (field (name "POWER") "0.0625W")
        (field (name "AUTHOR") "CERN DEM JLC")
      )
      (libsource (lib "") (part "Resistor - 1%_1"))
    )
    (comp (ref "R185")
      (value "1k2")
      (footprint "RESC1005X40N")
      (description "Resistor - 1%")
      (fields
        (field (name "PART NUMBER") "R0402_1K2_1%_0.0625W_100PPM")
        (field (name "POWER") "0.0625W")
        (field (name "AUTHOR") "CERN DEM JLC")
      )
      (libsource (lib "") (part "Resistor - 1%_1"))
    )
    (comp (ref "R186")
      (value "1k6")
      (footprint "RESC1005X40N")
      (description "Resistor - 1%")
      (fields
        (field (name "PART NUMBER") "R0402_1K6_1%_0.0625W_100PPM")
        (field (name "POWER") "0.0625W")
        (field (name "AUTHOR") "CERN DEM JLC")
      )
      (libsource (lib "") (part "Resistor - 1%_1"))
    )
    (comp (ref "R187")
      (value "10k")
      (footprint "RESC1005X40N")
      (description "Resistor - 1%")
      (fields
        (field (name "PART NUMBER") "R0402_10K_1%_0.0625W_100PPM")
        (field (name "POWER") "0.0625W")
        (field (name "AUTHOR") "CERN DEM JLC")
      )
      (libsource (lib "") (part "Resistor - 1%_1"))
    )
    (comp (ref "R188")
      (value "0")
      (footprint "RESC1005X40N")
      (description "Resistor")
      (fields
        (field (name "PART NUMBER") "R0402_0R_JUMPER")
        (field (name "MANUFACTURER") "GENERIC")
        (field (name "AUTHOR") "CERN DEM JLC")
      )
      (libsource (lib "Resistors") (part "Resistor"))
    )
    (comp (ref "R189")
      (value "33k")
      (footprint "RESC1005X40N")
      (description "Resistor - 1%")
      (fields
        (field (name "PART NUMBER") "R0402_33K_1%_0.0625W_100PPM")
        (field (name "POWER") "0.0625W")
        (field (name "AUTHOR") "CERN DEM JLC")
      )
      (libsource (lib "") (part "Resistor - 1%_1"))
    )
    (comp (ref "R190")
      (value "33k")
      (footprint "RESC1005X40N")
      (description "Resistor - 1%")
      (fields
        (field (name "PART NUMBER") "R0402_33K_1%_0.0625W_100PPM")
        (field (name "POWER") "0.0625W")
        (field (name "AUTHOR") "CERN DEM JLC")
      )
      (libsource (lib "") (part "Resistor - 1%_1"))
    )
    (comp (ref "R194")
      (value "0")
      (footprint "RESC1005X40N")
      (description "Resistor")
      (fields
        (field (name "PART NUMBER") "R0402_0R_JUMPER")
        (field (name "MANUFACTURER") "GENERIC")
        (field (name "AUTHOR") "CERN DEM JLC")
      )
      (libsource (lib "Resistors") (part "Resistor"))
    )
    (comp (ref "R197")
      (value "75k")
      (footprint "RESC1005X40N")
      (description "Resistor - 1%")
      (fields
        (field (name "PART NUMBER") "R0402_75K_1%_0.0625W_100PPM")
        (field (name "POWER") "0.0625W")
        (field (name "AUTHOR") "CERN DEM JLC")
      )
      (libsource (lib "") (part "Resistor - 1%_1"))
    )
    (comp (ref "R198")
      (value "75k")
      (footprint "RESC1005X40N")
      (description "Resistor - 1%")
      (fields
        (field (name "PART NUMBER") "R0402_75K_1%_0.0625W_100PPM")
        (field (name "POWER") "0.0625W")
        (field (name "AUTHOR") "CERN DEM JLC")
      )
      (libsource (lib "") (part "Resistor - 1%_1"))
    )
    (comp (ref "R199")
      (value "10k")
      (footprint "RESC1005X40N")
      (description "Resistor - 1%")
      (fields
        (field (name "PART NUMBER") "R0402_10K_1%_0.0625W_100PPM")
        (field (name "POWER") "0.0625W")
        (field (name "AUTHOR") "CERN DEM JLC")
      )
      (libsource (lib "") (part "Resistor - 1%_1"))
    )
    (comp (ref "R200")
      (value "75k")
      (footprint "RESC1005X40N")
      (description "Resistor - 1%")
      (fields
        (field (name "PART NUMBER") "R0402_75K_1%_0.0625W_100PPM")
        (field (name "POWER") "0.0625W")
        (field (name "AUTHOR") "CERN DEM JLC")
      )
      (libsource (lib "") (part "Resistor - 1%_1"))
    )
    (comp (ref "R201")
      (value "24k")
      (footprint "RESC1005X40N")
      (description "Resistor - 1%")
      (fields
        (field (name "PART NUMBER") "R0402_24K_1%_0.0625W_100PPM")
        (field (name "POWER") "0.0625W")
        (field (name "AUTHOR") "CERN DEM JLC")
      )
      (libsource (lib "") (part "Resistor - 1%_1"))
    )
    (comp (ref "T7")
      (value "FDC606P")
      (footprint "SOT95P275X110-6N")
      (description "P-Channel 1.8V Specified PowerTrench MOSFET")
      (fields (field (name "MANUFACTURER") "ON SEMICONDUCTOR") (field (name "AUTHOR") "CERN DEM HF"))
      (libsource (lib "ICs And Semiconductors") (part "FDC606P"))
    )
    (comp (ref "T8")
      (value "FDC606P")
      (footprint "SOT95P275X110-6N")
      (description "P-Channel 1.8V Specified PowerTrench MOSFET")
      (fields (field (name "MANUFACTURER") "ON SEMICONDUCTOR") (field (name "AUTHOR") "CERN DEM HF"))
      (libsource (lib "ICs And Semiconductors") (part "FDC606P"))
    )
    (comp (ref "T9")
      (value "BC847B")
      (footprint "SOT95P230X110-3N")
      (description "NPN Transistor")
      (fields (field (name "MANUFACTURER") "NXP SEMICONDUCTORS") (field (name "AUTHOR") "CERN DEM JLC"))
      (libsource (lib "ICs And Semiconductors") (part "NPN B1 E2 C3"))
    )
    (comp (ref "T10")
      (value "BC847B")
      (footprint "SOT95P230X110-3N")
      (description "NPN Transistor")
      (fields (field (name "MANUFACTURER") "NXP SEMICONDUCTORS") (field (name "AUTHOR") "CERN DEM JLC"))
      (libsource (lib "ICs And Semiconductors") (part "NPN B1 E2 C3"))
    )
    (comp (ref "TP5")
      (value "Test Point")
      (footprint "TPS127")
      (fields (field (name "PART NUMBER") "SMD_PAD_1.27X1.27MM") (field (name "AUTHOR") "CERN DEM JLC"))
      (libsource (lib "Eletro-mechanical") (part "Test Point"))
    )
    (comp (ref "TP6")
      (value "Test Point")
      (footprint "TPS127")
      (fields (field (name "PART NUMBER") "SMD_PAD_1.27X1.27MM") (field (name "AUTHOR") "CERN DEM JLC"))
      (libsource (lib "Eletro-mechanical") (part "Test Point"))
    )
    (comp (ref "TP7")
      (value "Test Point")
      (footprint "TPS127")
      (fields (field (name "PART NUMBER") "SMD_PAD_1.27X1.27MM") (field (name "AUTHOR") "CERN DEM JLC"))
      (libsource (lib "Eletro-mechanical") (part "Test Point"))
    )
    (comp (ref "TP8")
      (value "Test Point")
      (footprint "TPS127")
      (fields (field (name "PART NUMBER") "SMD_PAD_1.27X1.27MM") (field (name "AUTHOR") "CERN DEM JLC"))
      (libsource (lib "Eletro-mechanical") (part "Test Point"))
    )
    (comp (ref "TP9")
      (value "Test Point")
      (footprint "TPS127")
      (fields (field (name "PART NUMBER") "SMD_PAD_1.27X1.27MM") (field (name "AUTHOR") "CERN DEM JLC"))
      (libsource (lib "Eletro-mechanical") (part "Test Point"))
    )
    (comp (ref "TP10")
      (value "Test Point")
      (footprint "TPS127")
      (fields (field (name "PART NUMBER") "SMD_PAD_1.27X1.27MM") (field (name "AUTHOR") "CERN DEM JLC"))
      (libsource (lib "Eletro-mechanical") (part "Test Point"))
    )
    (comp (ref "TP11")
      (value "Test Point")
      (footprint "TPS127")
      (fields (field (name "PART NUMBER") "SMD_PAD_1.27X1.27MM") (field (name "AUTHOR") "CERN DEM JLC"))
      (libsource (lib "Eletro-mechanical") (part "Test Point"))
    )
    (comp (ref "TP12")
      (value "Test Point")
      (footprint "TPS127")
      (fields (field (name "PART NUMBER") "SMD_PAD_1.27X1.27MM") (field (name "AUTHOR") "CERN DEM JLC"))
      (libsource (lib "Eletro-mechanical") (part "Test Point"))
    )
    (comp (ref "TP13")
      (value "Test Point")
      (footprint "TPS127")
      (fields (field (name "PART NUMBER") "SMD_PAD_1.27X1.27MM") (field (name "AUTHOR") "CERN DEM JLC"))
      (libsource (lib "Eletro-mechanical") (part "Test Point"))
    )
    (comp (ref "TP14")
      (value "Test Point")
      (footprint "TPS127")
      (fields (field (name "PART NUMBER") "SMD_PAD_1.27X1.27MM") (field (name "AUTHOR") "CERN DEM JLC"))
      (libsource (lib "Eletro-mechanical") (part "Test Point"))
    )
  )
  (nets
    (net (code "2") (name "/EEM0_I2C.SCL") (class "Default")
      (node (ref "IC33") (pin "2") (pinfunction "SCL_2") (pintype "input"))
    )
    (net (code "3") (name "/EEM0_I2C.SDA") (class "Default")
      (node (ref "IC33") (pin "1") (pinfunction "SDA_1") (pintype "bidirectional"))
    )
    (net (code "5") (name "/P1V2LX") (class "Default")
      (node (ref "IC21") (pin "3") (pinfunction "SW_3") (pintype "output"))
      (node (ref "L19") (pin "1") (pinfunction "1_1") (pintype "passive"))
    )
    (net (code "6") (name "/P2V5LX") (class "Default")
      (node (ref "IC1") (pin "3") (pinfunction "SW_3") (pintype "output"))
      (node (ref "L22") (pin "1") (pinfunction "1_1") (pintype "passive"))
    )
    (net (code "7") (name "/P3V6_VOUT") (class "Default")
      (node (ref "C73") (pin "2") (pinfunction "2_2") (pintype "passive"))
      (node (ref "IC15") (pin "D1") (pinfunction "VOUT1_1_D1") (pintype "power_in"))
      (node (ref "IC15") (pin "E1") (pinfunction "VOUT1_2_E1") (pintype "power_in"))
      (node (ref "L2") (pin "1") (pinfunction "1_1") (pintype "passive"))
    )
    (net (code "8") (name "/P7V5_VOUT") (class "Default")
      (node (ref "C125") (pin "2") (pinfunction "2_2") (pintype "passive"))
      (node (ref "IC15") (pin "A1") (pinfunction "VOUT2_1_A1") (pintype "power_in"))
      (node (ref "IC15") (pin "B1") (pinfunction "VOUT2_2_B1") (pintype "power_in"))
      (node (ref "L15") (pin "1") (pinfunction "1_1") (pintype "passive"))
    )
    (net (code "9") (name "/PGOOD") (class "Default")
      (node (ref "IC11") (pin "9") (pinfunction "PG_9") (pintype "output"))
      (node (ref "IC15") (pin "B4") (pinfunction "PGOOD2_B4") (pintype "open_collector"))
      (node (ref "IC15") (pin "D4") (pinfunction "PGOOD1_D4") (pintype "open_collector"))
      (node (ref "IC16") (pin "4") (pinfunction "PG_4") (pintype "output"))
      (node (ref "IC18") (pin "4") (pinfunction "PG_4") (pintype "output"))
      (node (ref "IC19") (pin "7") (pinfunction "PG_7") (pintype "output"))
      (node (ref "IC7") (pin "9") (pinfunction "PG_9") (pintype "output"))
      (node (ref "LD7") (pin "2") (pinfunction "A_2") (pintype "passive"))
      (node (ref "R53") (pin "1") (pinfunction "1_1") (pintype "passive"))
    )
    (net (code "10") (name "/PSU_EN") (class "Default")
      (node (ref "IC15") (pin "B2") (pinfunction "RUN2_B2") (pintype "input"))
      (node (ref "IC15") (pin "D2") (pinfunction "RUN1_D2") (pintype "input"))
      (node (ref "R187") (pin "1") (pinfunction "1_1") (pintype "passive"))
      (node (ref "R188") (pin "2") (pinfunction "2_2") (pintype "passive"))
    )
    (net (code "11") (name "GND") (class "Default")
      (node (ref "B17") (pin "1") (pinfunction "1_1") (pintype "bidirectional"))
      (node (ref "B18") (pin "1") (pinfunction "1_1") (pintype "bidirectional"))
      (node (ref "B19") (pin "1") (pinfunction "1_1") (pintype "bidirectional"))
      (node (ref "B20") (pin "1") (pinfunction "1_1") (pintype "bidirectional"))
      (node (ref "B9") (pin "1") (pinfunction "1_1") (pintype "bidirectional"))
      (node (ref "C117") (pin "2") (pinfunction "2_2") (pintype "passive"))
      (node (ref "C119") (pin "2") (pinfunction "2_2") (pintype "passive"))
      (node (ref "C120") (pin "2") (pinfunction "2_2") (pintype "passive"))
      (node (ref "C125") (pin "1") (pinfunction "1_1") (pintype "passive"))
      (node (ref "C126") (pin "1") (pinfunction "1_1") (pintype "passive"))
      (node (ref "C127") (pin "2") (pinfunction "2_2") (pintype "passive"))
      (node (ref "C146") (pin "2") (pinfunction "2_2") (pintype "passive"))
      (node (ref "C147") (pin "1") (pinfunction "1_1") (pintype "passive"))
      (node (ref "C148") (pin "2") (pinfunction "2_2") (pintype "passive"))
      (node (ref "C149") (pin "2") (pinfunction "2_2") (pintype "passive"))
      (node (ref "C150") (pin "2") (pinfunction "2_2") (pintype "passive"))
      (node (ref "C151") (pin "2") (pinfunction "2_2") (pintype "passive"))
      (node (ref "C152") (pin "1") (pinfunction "1_1") (pintype "passive"))
      (node (ref "C153") (pin "1") (pinfunction "1_1") (pintype "passive"))
      (node (ref "C154") (pin "1") (pinfunction "1_1") (pintype "passive"))
      (node (ref "C155") (pin "2") (pinfunction "2_2") (pintype "passive"))
      (node (ref "C156") (pin "2") (pinfunction "2_2") (pintype "passive"))
      (node (ref "C157") (pin "1") (pinfunction "1_1") (pintype "passive"))
      (node (ref "C158") (pin "1") (pinfunction "1_1") (pintype "passive"))
      (node (ref "C159") (pin "1") (pinfunction "1_1") (pintype "passive"))
      (node (ref "C160") (pin "2") (pinfunction "2_2") (pintype "passive"))
      (node (ref "C162") (pin "1") (pinfunction "1_1") (pintype "passive"))
      (node (ref "C163") (pin "2") (pinfunction "2_2") (pintype "passive"))
      (node (ref "C164") (pin "2") (pinfunction "2_2") (pintype "passive"))
      (node (ref "C165") (pin "1") (pinfunction "1_1") (pintype "passive"))
      (node (ref "C166") (pin "1") (pinfunction "1_1") (pintype "passive"))
      (node (ref "C183") (pin "1") (pinfunction "1_1") (pintype "passive"))
      (node (ref "C2") (pin "1") (pinfunction "1_1") (pintype "passive"))
      (node (ref "C225") (pin "1") (pinfunction "1_1") (pintype "passive"))
      (node (ref "C226") (pin "2") (pinfunction "2_2") (pintype "passive"))
      (node (ref "C245") (pin "1") (pinfunction "1_1") (pintype "passive"))
      (node (ref "C3") (pin "1") (pinfunction "1_1") (pintype "passive"))
      (node (ref "C4") (pin "1") (pinfunction "1_1") (pintype "passive"))
      (node (ref "C63") (pin "2") (pinfunction "2_2") (pintype "passive"))
      (node (ref "C64") (pin "1") (pinfunction "1_1") (pintype "passive"))
      (node (ref "C67") (pin "1") (pinfunction "1_1") (pintype "passive"))
      (node (ref "C70") (pin "1") (pinfunction "1_1") (pintype "passive"))
      (node (ref "C73") (pin "1") (pinfunction "1_1") (pintype "passive"))
      (node (ref "C74") (pin "2") (pinfunction "2_2") (pintype "passive"))
      (node (ref "C75") (pin "1") (pinfunction "1_1") (pintype "passive"))
      (node (ref "C77") (pin "1") (pinfunction "1_1") (pintype "passive"))
      (node (ref "C78") (pin "1") (pinfunction "1_1") (pintype "passive"))
      (node (ref "C79") (pin "1") (pinfunction "1_1") (pintype "passive"))
      (node (ref "IC1") (pin "2") (pinfunction "GND_2") (pintype "power_in"))
      (node (ref "IC11") (pin "12") (pinfunction "GND_12") (pintype "power_in"))
      (node (ref "IC11") (pin "21") (pinfunction "GND_21") (pintype "power_in"))
      (node (ref "IC15") (pin "B5") (pinfunction "GND_1_B5") (pintype "power_in"))
      (node (ref "IC15") (pin "C1") (pinfunction "GND_2_C1") (pintype "power_in"))
      (node (ref "IC15") (pin "C2") (pinfunction "GND_3_C2") (pintype "power_in"))
      (node (ref "IC15") (pin "C5") (pinfunction "SYNC/MODE_C5") (pintype "input"))
      (node (ref "IC15") (pin "D5") (pinfunction "GND_4_D5") (pintype "power_in"))
      (node (ref "IC16") (pin "11") (pinfunction "GND_11") (pintype "power_in"))
      (node (ref "IC16") (pin "5") (pinfunction "ILIM_5") (pintype "input"))
      (node (ref "IC16") (pin "8") (pinfunction "GND_8") (pintype "power_in"))
      (node (ref "IC18") (pin "11") (pinfunction "GND_11") (pintype "power_in"))
      (node (ref "IC18") (pin "5") (pinfunction "ILIM_5") (pintype "input"))
      (node (ref "IC18") (pin "8") (pinfunction "GND_8") (pintype "power_in"))
      (node (ref "IC19") (pin "11") (pinfunction "FSEL_11") (pintype "input"))
      (node (ref "IC19") (pin "3") (pinfunction "GND_3") (pintype "power_in"))
      (node (ref "IC19") (pin "4") (pinfunction "AGND_4") (pintype "power_in"))
      (node (ref "IC21") (pin "2") (pinfunction "GND_2") (pintype "power_in"))
      (node (ref "IC31") (pin "2") (pinfunction "GND_2") (pintype "power_in"))
      (node (ref "IC33") (pin "4") (pinfunction "GND_4") (pintype "power_in"))
      (node (ref "IC33") (pin "5") (pinfunction "A2_5") (pintype "input"))
      (node (ref "IC33") (pin "6") (pinfunction "A1_6") (pintype "input"))
      (node (ref "IC7") (pin "12") (pinfunction "GND_12") (pintype "power_in"))
      (node (ref "IC7") (pin "21") (pinfunction "GND_21") (pintype "power_in"))
      (node (ref "LD10") (pin "1") (pinfunction "C_1") (pintype "passive"))
      (node (ref "LD11") (pin "1") (pinfunction "C_1") (pintype "passive"))
      (node (ref "LD12") (pin "1") (pinfunction "C_1") (pintype "passive"))
      (node (ref "LD3") (pin "1") (pinfunction "C_1") (pintype "passive"))
      (node (ref "LD4") (pin "1") (pinfunction "C_1") (pintype "passive"))
      (node (ref "LD7") (pin "1") (pinfunction "C_1") (pintype "passive"))
      (node (ref "LD9") (pin "1") (pinfunction "C_1") (pintype "passive"))
      (node (ref "R104") (pin "1") (pinfunction "1_1") (pintype "passive"))
      (node (ref "R105") (pin "1") (pinfunction "1_1") (pintype "passive"))
      (node (ref "R107") (pin "2") (pinfunction "2_2") (pintype "passive"))
      (node (ref "R119") (pin "1") (pinfunction "1_1") (pintype "passive"))
      (node (ref "R131") (pin "1") (pinfunction "1_1") (pintype "passive"))
      (node (ref "R132") (pin "1") (pinfunction "1_1") (pintype "passive"))
      (node (ref "R136") (pin "1") (pinfunction "1_1") (pintype "passive"))
      (node (ref "R179") (pin "1") (pinfunction "1_1") (pintype "passive"))
      (node (ref "R194") (pin "1") (pinfunction "1_1") (pintype "passive"))
      (node (ref "R200") (pin "1") (pinfunction "1_1") (pintype "passive"))
      (node (ref "R201") (pin "1") (pinfunction "1_1") (pintype "passive"))
      (node (ref "R55") (pin "2") (pinfunction "2_2") (pintype "passive"))
      (node (ref "R80") (pin "1") (pinfunction "1_1") (pintype "passive"))
      (node (ref "R82") (pin "2") (pinfunction "2_2") (pintype "passive"))
      (node (ref "T10") (pin "2") (pinfunction "E_2") (pintype "passive"))
      (node (ref "T9") (pin "2") (pinfunction "E_2") (pintype "passive"))
    )
    (net (code "12") (name "Net-(IC1-EN)") (class "Default")
      (node (ref "C4") (pin "2") (pinfunction "2_2") (pintype "passive"))
      (node (ref "IC1") (pin "1") (pinfunction "EN_1") (pintype "input"))
      (node (ref "R199") (pin "2") (pinfunction "2_2") (pintype "passive"))
    )
    (net (code "13") (name "Net-(IC1-FB)") (class "Default")
      (node (ref "IC1") (pin "5") (pinfunction "FB_5") (pintype "input"))
      (node (ref "R198") (pin "1") (pinfunction "1_1") (pintype "passive"))
      (node (ref "R201") (pin "2") (pinfunction "2_2") (pintype "passive"))
    )
    (net (code "14") (name "Net-(IC7-FB)") (class "Default")
      (node (ref "IC7") (pin "16") (pinfunction "FB_16") (pintype "input"))
      (node (ref "R23") (pin "1") (pinfunction "1_1") (pintype "passive"))
      (node (ref "R80") (pin "2") (pinfunction "2_2") (pintype "passive"))
    )
    (net (code "15") (name "Net-(IC11-FB)") (class "Default")
      (node (ref "IC11") (pin "16") (pinfunction "FB_16") (pintype "input"))
      (node (ref "R118") (pin "1") (pinfunction "1_1") (pintype "passive"))
      (node (ref "R119") (pin "2") (pinfunction "2_2") (pintype "passive"))
    )
    (net (code "16") (name "Net-(IC15-COMP1)") (class "Default")
      (node (ref "IC15") (pin "E5") (pinfunction "COMP1_E5") (pintype "passive"))
      (node (ref "TP6") (pin "1") (pinfunction "1_1") (pintype "bidirectional"))
    )
    (net (code "17") (name "Net-(IC15-COMP2)") (class "Default")
      (node (ref "IC15") (pin "A5") (pinfunction "COMP2_A5") (pintype "passive"))
      (node (ref "TP8") (pin "1") (pinfunction "1_1") (pintype "bidirectional"))
    )
    (net (code "18") (name "Net-(IC15-FB1)") (class "Default")
      (node (ref "IC15") (pin "E4") (pinfunction "FB1_E4") (pintype "input"))
      (node (ref "R55") (pin "1") (pinfunction "1_1") (pintype "passive"))
      (node (ref "R82") (pin "1") (pinfunction "1_1") (pintype "passive"))
    )
    (net (code "19") (name "Net-(IC15-FB2)") (class "Default")
      (node (ref "IC15") (pin "A4") (pinfunction "FB2_A4") (pintype "input"))
      (node (ref "R108") (pin "1") (pinfunction "1_1") (pintype "passive"))
    )
    (net (code "20") (name "Net-(IC15-FREQ)") (class "Default")
      (node (ref "IC15") (pin "C4") (pinfunction "FREQ_C4") (pintype "input"))
      (node (ref "TP7") (pin "1") (pinfunction "1_1") (pintype "bidirectional"))
    )
    (net (code "21") (name "Net-(IC15-INTVCC)") (class "Default")
      (node (ref "IC15") (pin "C3") (pinfunction "INTVCC_C3") (pintype "input"))
      (node (ref "TP5") (pin "1") (pinfunction "1_1") (pintype "bidirectional"))
    )
    (net (code "22") (name "Net-(IC15-TRACK{slash}SS1)") (class "Default")
      (node (ref "C67") (pin "2") (pinfunction "2_2") (pintype "passive"))
      (node (ref "IC15") (pin "A3") (pinfunction "TRACK/SS2_A3") (pintype "input"))
      (node (ref "IC15") (pin "E3") (pinfunction "TRACK/SS1_E3") (pintype "input"))
    )
    (net (code "23") (name "Net-(IC16-PGFB)") (class "Default")
      (node (ref "IC16") (pin "6") (pinfunction "PGFB_6") (pintype "input"))
      (node (ref "R179") (pin "2") (pinfunction "2_2") (pintype "passive"))
      (node (ref "R180") (pin "1") (pinfunction "1_1") (pintype "passive"))
    )
    (net (code "24") (name "Net-(IC16-SET)") (class "Default")
      (node (ref "C146") (pin "1") (pinfunction "1_1") (pintype "passive"))
      (node (ref "IC16") (pin "7") (pinfunction "SET_7") (pintype "input"))
      (node (ref "R104") (pin "2") (pinfunction "2_2") (pintype "passive"))
      (node (ref "R105") (pin "2") (pinfunction "2_2") (pintype "passive"))
    )
    (net (code "25") (name "Net-(IC18-PGFB)") (class "Default")
      (node (ref "IC18") (pin "6") (pinfunction "PGFB_6") (pintype "input"))
      (node (ref "R132") (pin "2") (pinfunction "2_2") (pintype "passive"))
      (node (ref "R133") (pin "1") (pinfunction "1_1") (pintype "passive"))
    )
    (net (code "26") (name "Net-(IC18-SET)") (class "Default")
      (node (ref "C151") (pin "1") (pinfunction "1_1") (pintype "passive"))
      (node (ref "IC18") (pin "7") (pinfunction "SET_7") (pintype "input"))
      (node (ref "R114") (pin "2") (pinfunction "2_2") (pintype "passive"))
    )
    (net (code "27") (name "Net-(IC19-FB)") (class "Default")
      (node (ref "IC19") (pin "5") (pinfunction "FB_5") (pintype "input"))
      (node (ref "R135") (pin "1") (pinfunction "1_1") (pintype "passive"))
      (node (ref "R136") (pin "2") (pinfunction "2_2") (pintype "passive"))
    )
    (net (code "28") (name "Net-(IC19-MODE)") (class "Default")
      (node (ref "IC19") (pin "10") (pinfunction "MODE_10") (pintype "input"))
      (node (ref "R134") (pin "1") (pinfunction "1_1") (pintype "passive"))
    )
    (net (code "29") (name "Net-(IC19-SS{slash}TR)") (class "Default")
      (node (ref "C155") (pin "1") (pinfunction "1_1") (pintype "passive"))
      (node (ref "IC19") (pin "9") (pinfunction "SS/TR_9") (pintype "input"))
    )
    (net (code "30") (name "Net-(IC19-SW)") (class "Default")
      (node (ref "IC19") (pin "2") (pinfunction "SW_2") (pintype "output"))
      (node (ref "L4") (pin "1") (pinfunction "1_1") (pintype "passive"))
    )
    (net (code "31") (name "Net-(IC21-FB)") (class "Default")
      (node (ref "IC21") (pin "5") (pinfunction "FB_5") (pintype "input"))
      (node (ref "R197") (pin "1") (pinfunction "1_1") (pintype "passive"))
      (node (ref "R200") (pin "2") (pinfunction "2_2") (pintype "passive"))
    )
    (net (code "32") (name "Net-(IC33-A0)") (class "Default")
      (node (ref "IC33") (pin "7") (pinfunction "A0_7") (pintype "input"))
      (node (ref "R194") (pin "2") (pinfunction "2_2") (pintype "passive"))
    )
    (net (code "33") (name "Net-(IC33-O.S.)") (class "Default")
      (node (ref "IC33") (pin "3") (pinfunction "O.S._3") (pintype "output"))
      (node (ref "LD7") (pin "3") (pinfunction "C_3") (pintype "passive"))
      (node (ref "R188") (pin "1") (pinfunction "1_1") (pintype "passive"))
    )
    (net (code "34") (name "Net-(LD3-A)") (class "Default")
      (node (ref "LD3") (pin "2") (pinfunction "A_2") (pintype "passive"))
      (node (ref "R181") (pin "2") (pinfunction "2_2") (pintype "passive"))
    )
    (net (code "35") (name "Net-(LD4-A)") (class "Default")
      (node (ref "LD4") (pin "2") (pinfunction "A_2") (pintype "passive"))
      (node (ref "R184") (pin "2") (pinfunction "2_2") (pintype "passive"))
    )
    (net (code "36") (name "Net-(LD7B-A)") (class "Default")
      (node (ref "LD7") (pin "4") (pinfunction "A_4") (pintype "passive"))
      (node (ref "R186") (pin "1") (pinfunction "1_1") (pintype "passive"))
    )
    (net (code "37") (name "Net-(LD9-A)") (class "Default")
      (node (ref "LD9") (pin "2") (pinfunction "A_2") (pintype "passive"))
      (node (ref "R139") (pin "1") (pinfunction "1_1") (pintype "passive"))
    )
    (net (code "38") (name "Net-(LD10-A)") (class "Default")
      (node (ref "LD10") (pin "2") (pinfunction "A_2") (pintype "passive"))
      (node (ref "R185") (pin "2") (pinfunction "2_2") (pintype "passive"))
    )
    (net (code "39") (name "Net-(LD11-A)") (class "Default")
      (node (ref "LD11") (pin "2") (pinfunction "A_2") (pintype "passive"))
      (node (ref "R178") (pin "2") (pinfunction "2_2") (pintype "passive"))
    )
    (net (code "40") (name "Net-(LD12-A)") (class "Default")
      (node (ref "LD12") (pin "2") (pinfunction "A_2") (pintype "passive"))
      (node (ref "R109") (pin "1") (pinfunction "1_1") (pintype "passive"))
    )
    (net (code "41") (name "Net-(R107-Pad1)") (class "Default")
      (node (ref "R107") (pin "1") (pinfunction "1_1") (pintype "passive"))
      (node (ref "R108") (pin "2") (pinfunction "2_2") (pintype "passive"))
    )
    (net (code "42") (name "Net-(R114-Pad1)") (class "Default")
      (node (ref "R114") (pin "1") (pinfunction "1_1") (pintype "passive"))
      (node (ref "R131") (pin "2") (pinfunction "2_2") (pintype "passive"))
    )
    (net (code "43") (name "Net-(T9-B)") (class "Default")
      (node (ref "C159") (pin "2") (pinfunction "2_2") (pintype "passive"))
      (node (ref "R189") (pin "2") (pinfunction "2_2") (pintype "passive"))
      (node (ref "T9") (pin "1") (pinfunction "B_1") (pintype "passive"))
    )
    (net (code "44") (name "Net-(T9-C)") (class "Default")
      (node (ref "R182") (pin "1") (pinfunction "1_1") (pintype "passive"))
      (node (ref "T7") (pin "3") (pinfunction "S_3") (pintype "passive"))
      (node (ref "T9") (pin "3") (pinfunction "C_3") (pintype "passive"))
    )
    (net (code "45") (name "Net-(T10-B)") (class "Default")
      (node (ref "C2") (pin "2") (pinfunction "2_2") (pintype "passive"))
      (node (ref "R190") (pin "2") (pinfunction "2_2") (pintype "passive"))
      (node (ref "T10") (pin "1") (pinfunction "B_1") (pintype "passive"))
    )
    (net (code "46") (name "Net-(T10-C)") (class "Default")
      (node (ref "R183") (pin "1") (pinfunction "1_1") (pintype "passive"))
      (node (ref "T10") (pin "3") (pinfunction "C_3") (pintype "passive"))
      (node (ref "T8") (pin "3") (pinfunction "S_3") (pintype "passive"))
    )
    (net (code "47") (name "P1V2") (class "Default")
      (node (ref "B15") (pin "1") (pinfunction "1_1") (pintype "bidirectional"))
      (node (ref "C163") (pin "1") (pinfunction "1_1") (pintype "passive"))
      (node (ref "L19") (pin "2") (pinfunction "2_2") (pintype "passive"))
      (node (ref "R189") (pin "1") (pinfunction "1_1") (pintype "passive"))
      (node (ref "R197") (pin "2") (pinfunction "2_2") (pintype "passive"))
    )
    (net (code "48") (name "P2V5") (class "Default")
      (node (ref "B16") (pin "1") (pinfunction "1_1") (pintype "bidirectional"))
      (node (ref "C164") (pin "1") (pinfunction "1_1") (pintype "passive"))
      (node (ref "L22") (pin "2") (pinfunction "2_2") (pintype "passive"))
      (node (ref "R190") (pin "1") (pinfunction "1_1") (pintype "passive"))
      (node (ref "R198") (pin "2") (pinfunction "2_2") (pintype "passive"))
    )
    (net (code "49") (name "P3V3") (class "Default")
      (node (ref "B13") (pin "1") (pinfunction "1_1") (pintype "bidirectional"))
      (node (ref "R184") (pin "1") (pinfunction "1_1") (pintype "passive"))
      (node (ref "T8") (pin "1") (pinfunction "D_1") (pintype "passive"))
      (node (ref "T8") (pin "2") (pinfunction "D_2") (pintype "passive"))
      (node (ref "T8") (pin "5") (pinfunction "D_5") (pintype "passive"))
      (node (ref "T8") (pin "6") (pinfunction "D_6") (pintype "passive"))
      (node (ref "TP9") (pin "1") (pinfunction "1_1") (pintype "bidirectional"))
    )
    (net (code "50") (name "P3V3A") (class "Default")
      (node (ref "B5") (pin "1") (pinfunction "1_1") (pintype "bidirectional"))
      (node (ref "C78") (pin "2") (pinfunction "2_2") (pintype "passive"))
      (node (ref "IC7") (pin "1") (pinfunction "OUT_1") (pintype "power_in"))
      (node (ref "IC7") (pin "18") (pinfunction "OUT_18") (pintype "power_in"))
      (node (ref "IC7") (pin "19") (pinfunction "OUT_19") (pintype "power_in"))
      (node (ref "IC7") (pin "20") (pinfunction "OUT_20") (pintype "power_in"))
      (node (ref "R178") (pin "1") (pinfunction "1_1") (pintype "passive"))
      (node (ref "R23") (pin "2") (pinfunction "2_2") (pintype "passive"))
      (node (ref "TP10") (pin "1") (pinfunction "1_1") (pintype "bidirectional"))
    )
    (net (code "51") (name "P3V3_DIOT") (class "Default")
      (node (ref "B6") (pin "1") (pinfunction "1_1") (pintype "bidirectional"))
      (node (ref "C226") (pin "1") (pinfunction "1_1") (pintype "passive"))
      (node (ref "D11") (pin "2") (pinfunction "A_2") (pintype "passive"))
      (node (ref "IC31") (pin "5") (pinfunction "OUT_5") (pintype "power_in"))
    )
    (net (code "52") (name "P3V3_INIT") (class "Default")
      (node (ref "B12") (pin "1") (pinfunction "1_1") (pintype "bidirectional"))
      (node (ref "R199") (pin "1") (pinfunction "1_1") (pintype "passive"))
      (node (ref "T7") (pin "1") (pinfunction "D_1") (pintype "passive"))
      (node (ref "T7") (pin "2") (pinfunction "D_2") (pintype "passive"))
      (node (ref "T7") (pin "5") (pinfunction "D_5") (pintype "passive"))
      (node (ref "T7") (pin "6") (pinfunction "D_6") (pintype "passive"))
    )
    (net (code "53") (name "P3V3_MP") (class "Default")
      (node (ref "B7") (pin "1") (pinfunction "1_1") (pintype "bidirectional"))
      (node (ref "C245") (pin "2") (pinfunction "2_2") (pintype "passive"))
      (node (ref "D11") (pin "1") (pinfunction "C_1") (pintype "passive"))
      (node (ref "IC33") (pin "8") (pinfunction "+VS_8") (pintype "power_in"))
      (node (ref "R185") (pin "1") (pinfunction "1_1") (pintype "passive"))
      (node (ref "R186") (pin "2") (pinfunction "2_2") (pintype "passive"))
      (node (ref "R187") (pin "2") (pinfunction "2_2") (pintype "passive"))
      (node (ref "TP11") (pin "1") (pinfunction "1_1") (pintype "bidirectional"))
    )
    (net (code "54") (name "P3V3_buck") (class "Default")
      (node (ref "C162") (pin "2") (pinfunction "2_2") (pintype "passive"))
      (node (ref "C166") (pin "2") (pinfunction "2_2") (pintype "passive"))
      (node (ref "C3") (pin "2") (pinfunction "2_2") (pintype "passive"))
      (node (ref "IC1") (pin "4") (pinfunction "VIN_4") (pintype "input"))
      (node (ref "IC11") (pin "1") (pinfunction "OUT_1") (pintype "power_in"))
      (node (ref "IC11") (pin "18") (pinfunction "OUT_18") (pintype "power_in"))
      (node (ref "IC11") (pin "19") (pinfunction "OUT_19") (pintype "power_in"))
      (node (ref "IC11") (pin "20") (pinfunction "OUT_20") (pintype "power_in"))
      (node (ref "IC21") (pin "1") (pinfunction "EN_1") (pintype "input"))
      (node (ref "IC21") (pin "4") (pinfunction "VIN_4") (pintype "input"))
      (node (ref "R118") (pin "2") (pinfunction "2_2") (pintype "passive"))
      (node (ref "R182") (pin "2") (pinfunction "2_2") (pintype "passive"))
      (node (ref "R183") (pin "2") (pinfunction "2_2") (pintype "passive"))
      (node (ref "T7") (pin "4") (pinfunction "S_4") (pintype "passive"))
      (node (ref "T8") (pin "4") (pinfunction "S_4") (pintype "passive"))
    )
    (net (code "55") (name "P3V6") (class "Default")
      (node (ref "B4") (pin "1") (pinfunction "1_1") (pintype "bidirectional"))
      (node (ref "C160") (pin "1") (pinfunction "1_1") (pintype "passive"))
      (node (ref "C63") (pin "1") (pinfunction "1_1") (pintype "passive"))
      (node (ref "C74") (pin "1") (pinfunction "1_1") (pintype "passive"))
      (node (ref "C75") (pin "2") (pinfunction "2_2") (pintype "passive"))
      (node (ref "IC11") (pin "5") (pinfunction "IN_5") (pintype "input"))
      (node (ref "IC11") (pin "6") (pinfunction "IN_6") (pintype "input"))
      (node (ref "IC11") (pin "7") (pinfunction "IN_7") (pintype "input"))
      (node (ref "IC11") (pin "8") (pinfunction "IN_8") (pintype "input"))
      (node (ref "IC7") (pin "5") (pinfunction "IN_5") (pintype "input"))
      (node (ref "IC7") (pin "6") (pinfunction "IN_6") (pintype "input"))
      (node (ref "IC7") (pin "7") (pinfunction "IN_7") (pintype "input"))
      (node (ref "IC7") (pin "8") (pinfunction "IN_8") (pintype "input"))
      (node (ref "L2") (pin "2") (pinfunction "2_2") (pintype "passive"))
    )
    (net (code "56") (name "P5V0A") (class "Default")
      (node (ref "B11") (pin "1") (pinfunction "1_1") (pintype "bidirectional"))
      (node (ref "C119") (pin "1") (pinfunction "1_1") (pintype "passive"))
      (node (ref "C120") (pin "1") (pinfunction "1_1") (pintype "passive"))
      (node (ref "C165") (pin "2") (pinfunction "2_2") (pintype "passive"))
      (node (ref "C77") (pin "2") (pinfunction "2_2") (pintype "passive"))
      (node (ref "C79") (pin "2") (pinfunction "2_2") (pintype "passive"))
      (node (ref "IC11") (pin "10") (pinfunction "BIAS_10") (pintype "input"))
      (node (ref "IC11") (pin "11") (pinfunction "EN_11") (pintype "input"))
      (node (ref "IC16") (pin "10") (pinfunction "OUT_10") (pintype "output"))
      (node (ref "IC16") (pin "9") (pinfunction "OUTS_9") (pintype "output"))
      (node (ref "IC7") (pin "10") (pinfunction "BIAS_10") (pintype "input"))
      (node (ref "IC7") (pin "11") (pinfunction "EN_11") (pintype "input"))
      (node (ref "R139") (pin "2") (pinfunction "2_2") (pintype "passive"))
      (node (ref "R180") (pin "2") (pinfunction "2_2") (pintype "passive"))
      (node (ref "TP12") (pin "1") (pinfunction "1_1") (pintype "bidirectional"))
    )
    (net (code "57") (name "P5V5") (class "Default")
      (node (ref "C152") (pin "2") (pinfunction "2_2") (pintype "passive"))
      (node (ref "C153") (pin "2") (pinfunction "2_2") (pintype "passive"))
      (node (ref "C154") (pin "2") (pinfunction "2_2") (pintype "passive"))
      (node (ref "IC19") (pin "6") (pinfunction "VOS_6") (pintype "input"))
      (node (ref "L4") (pin "2") (pinfunction "2_2") (pintype "passive"))
      (node (ref "L5") (pin "1") (pinfunction "1_1") (pintype "passive"))
      (node (ref "R135") (pin "2") (pinfunction "2_2") (pintype "passive"))
    )
    (net (code "58") (name "P5V5A") (class "Default")
      (node (ref "B10") (pin "1") (pinfunction "1_1") (pintype "bidirectional"))
      (node (ref "C117") (pin "1") (pinfunction "1_1") (pintype "passive"))
      (node (ref "C156") (pin "1") (pinfunction "1_1") (pintype "passive"))
      (node (ref "C183") (pin "2") (pinfunction "2_2") (pintype "passive"))
      (node (ref "IC16") (pin "1") (pinfunction "IN_1") (pintype "input"))
      (node (ref "IC16") (pin "2") (pinfunction "IN_2") (pintype "input"))
      (node (ref "IC16") (pin "3") (pinfunction "EN/UV_3") (pintype "input"))
      (node (ref "L5") (pin "2") (pinfunction "2_2") (pintype "passive"))
    )
    (net (code "59") (name "P7V0A") (class "Default")
      (node (ref "B14") (pin "1") (pinfunction "1_1") (pintype "bidirectional"))
      (node (ref "C147") (pin "2") (pinfunction "2_2") (pintype "passive"))
      (node (ref "C149") (pin "1") (pinfunction "1_1") (pintype "passive"))
      (node (ref "C150") (pin "1") (pinfunction "1_1") (pintype "passive"))
      (node (ref "IC18") (pin "10") (pinfunction "OUT_10") (pintype "output"))
      (node (ref "IC18") (pin "9") (pinfunction "OUTS_9") (pintype "output"))
      (node (ref "R109") (pin "2") (pinfunction "2_2") (pintype "passive"))
      (node (ref "R133") (pin "2") (pinfunction "2_2") (pintype "passive"))
      (node (ref "TP13") (pin "1") (pinfunction "1_1") (pintype "bidirectional"))
    )
    (net (code "60") (name "P7V5") (class "Default")
      (node (ref "B8") (pin "1") (pinfunction "1_1") (pintype "bidirectional"))
      (node (ref "C126") (pin "2") (pinfunction "2_2") (pintype "passive"))
      (node (ref "C127") (pin "1") (pinfunction "1_1") (pintype "passive"))
      (node (ref "C148") (pin "1") (pinfunction "1_1") (pintype "passive"))
      (node (ref "IC18") (pin "1") (pinfunction "IN_1") (pintype "input"))
      (node (ref "IC18") (pin "2") (pinfunction "IN_2") (pintype "input"))
      (node (ref "IC18") (pin "3") (pinfunction "EN/UV_3") (pintype "input"))
      (node (ref "L15") (pin "2") (pinfunction "2_2") (pintype "passive"))
      (node (ref "R53") (pin "2") (pinfunction "2_2") (pintype "passive"))
    )
    (net (code "61") (name "P12V0") (class "Default")
      (node (ref "B3") (pin "1") (pinfunction "1_1") (pintype "bidirectional"))
      (node (ref "C157") (pin "2") (pinfunction "2_2") (pintype "passive"))
      (node (ref "C158") (pin "2") (pinfunction "2_2") (pintype "passive"))
      (node (ref "C64") (pin "2") (pinfunction "2_2") (pintype "passive"))
      (node (ref "C70") (pin "2") (pinfunction "2_2") (pintype "passive"))
      (node (ref "IC15") (pin "A2") (pinfunction "VIN_1_A2") (pintype "power_in"))
      (node (ref "IC15") (pin "B3") (pinfunction "VIN_2_B3") (pintype "power_in"))
      (node (ref "IC15") (pin "D3") (pinfunction "VIN_3_D3") (pintype "power_in"))
      (node (ref "IC15") (pin "E2") (pinfunction "VIN_4_E2") (pintype "power_in"))
      (node (ref "IC19") (pin "1") (pinfunction "VIN_1") (pintype "input"))
      (node (ref "IC19") (pin "8") (pinfunction "EN_8") (pintype "input"))
      (node (ref "R134") (pin "2") (pinfunction "2_2") (pintype "passive"))
      (node (ref "R181") (pin "1") (pinfunction "1_1") (pintype "passive"))
      (node (ref "TP14") (pin "1") (pinfunction "1_1") (pintype "bidirectional"))
    )
    (net (code "62") (name "P12V0_DIOT") (class "Default")
      (node (ref "C225") (pin "2") (pinfunction "2_2") (pintype "passive"))
      (node (ref "IC31") (pin "1") (pinfunction "IN_1") (pintype "input"))
      (node (ref "IC31") (pin "3") (pinfunction "EN_3") (pintype "input"))
    )
    (net (code "63") (name "unconnected-(IC7-NC-Pad2)") (class "Default")
      (node (ref "IC7") (pin "2") (pinfunction "NC_2") (pintype "passive+no_connect"))
    )
    (net (code "64") (name "unconnected-(IC7-NC-Pad3)") (class "Default")
      (node (ref "IC7") (pin "3") (pinfunction "NC_3") (pintype "passive+no_connect"))
    )
    (net (code "65") (name "unconnected-(IC7-NC-Pad4)") (class "Default")
      (node (ref "IC7") (pin "4") (pinfunction "NC_4") (pintype "passive+no_connect"))
    )
    (net (code "66") (name "unconnected-(IC7-NC-Pad13)") (class "Default")
      (node (ref "IC7") (pin "13") (pinfunction "NC_13") (pintype "passive+no_connect"))
    )
    (net (code "67") (name "unconnected-(IC7-NC-Pad14)") (class "Default")
      (node (ref "IC7") (pin "14") (pinfunction "NC_14") (pintype "passive+no_connect"))
    )
    (net (code "68") (name "unconnected-(IC7-NC-Pad17)") (class "Default")
      (node (ref "IC7") (pin "17") (pinfunction "NC_17") (pintype "passive+no_connect"))
    )
    (net (code "69") (name "unconnected-(IC7-SS-Pad15)") (class "Default")
      (node (ref "IC7") (pin "15") (pinfunction "SS_15") (pintype "output+no_connect"))
    )
    (net (code "70") (name "unconnected-(IC11-NC-Pad2)") (class "Default")
      (node (ref "IC11") (pin "2") (pinfunction "NC_2") (pintype "passive+no_connect"))
    )
    (net (code "71") (name "unconnected-(IC11-NC-Pad3)") (class "Default")
      (node (ref "IC11") (pin "3") (pinfunction "NC_3") (pintype "passive+no_connect"))
    )
    (net (code "72") (name "unconnected-(IC11-NC-Pad4)") (class "Default")
      (node (ref "IC11") (pin "4") (pinfunction "NC_4") (pintype "passive+no_connect"))
    )
    (net (code "73") (name "unconnected-(IC11-NC-Pad13)") (class "Default")
      (node (ref "IC11") (pin "13") (pinfunction "NC_13") (pintype "passive+no_connect"))
    )
    (net (code "74") (name "unconnected-(IC11-NC-Pad14)") (class "Default")
      (node (ref "IC11") (pin "14") (pinfunction "NC_14") (pintype "passive+no_connect"))
    )
    (net (code "75") (name "unconnected-(IC11-NC-Pad17)") (class "Default")
      (node (ref "IC11") (pin "17") (pinfunction "NC_17") (pintype "passive+no_connect"))
    )
    (net (code "76") (name "unconnected-(IC11-SS-Pad15)") (class "Default")
      (node (ref "IC11") (pin "15") (pinfunction "SS_15") (pintype "output+no_connect"))
    )
    (net (code "77") (name "unconnected-(IC31-BYP-Pad4)") (class "Default")
      (node (ref "IC31") (pin "4") (pinfunction "BYP_4") (pintype "passive+no_connect"))
    )
  )
)
